# Callisto_Teknic_MSO_LED_out_v2.net
KiCad netlist of a schematic drawn in EAGLE
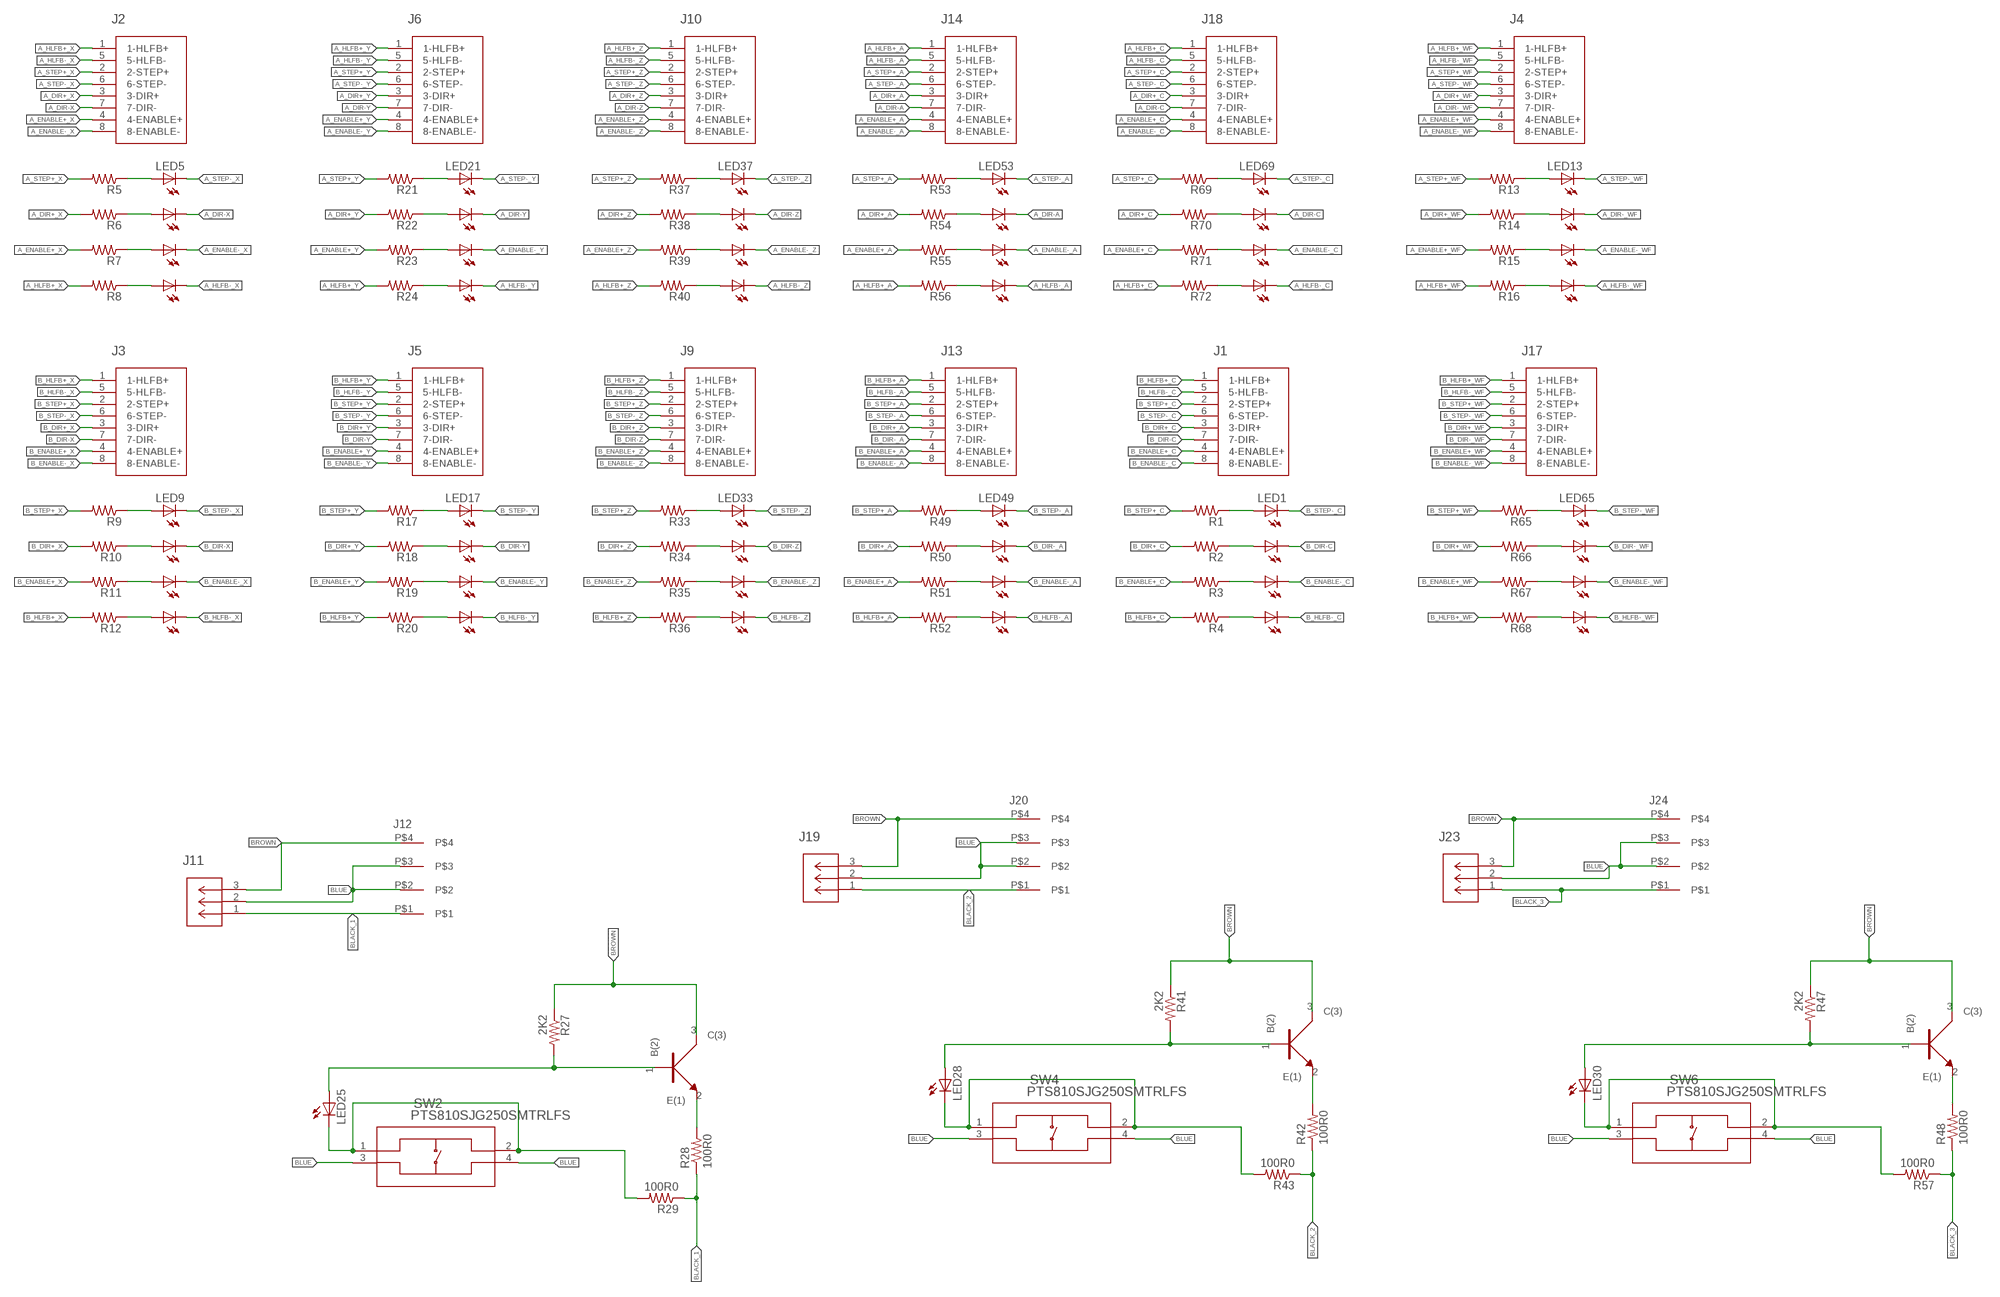
[diagram p0: schematic, sheet 1, part 1 of 2]
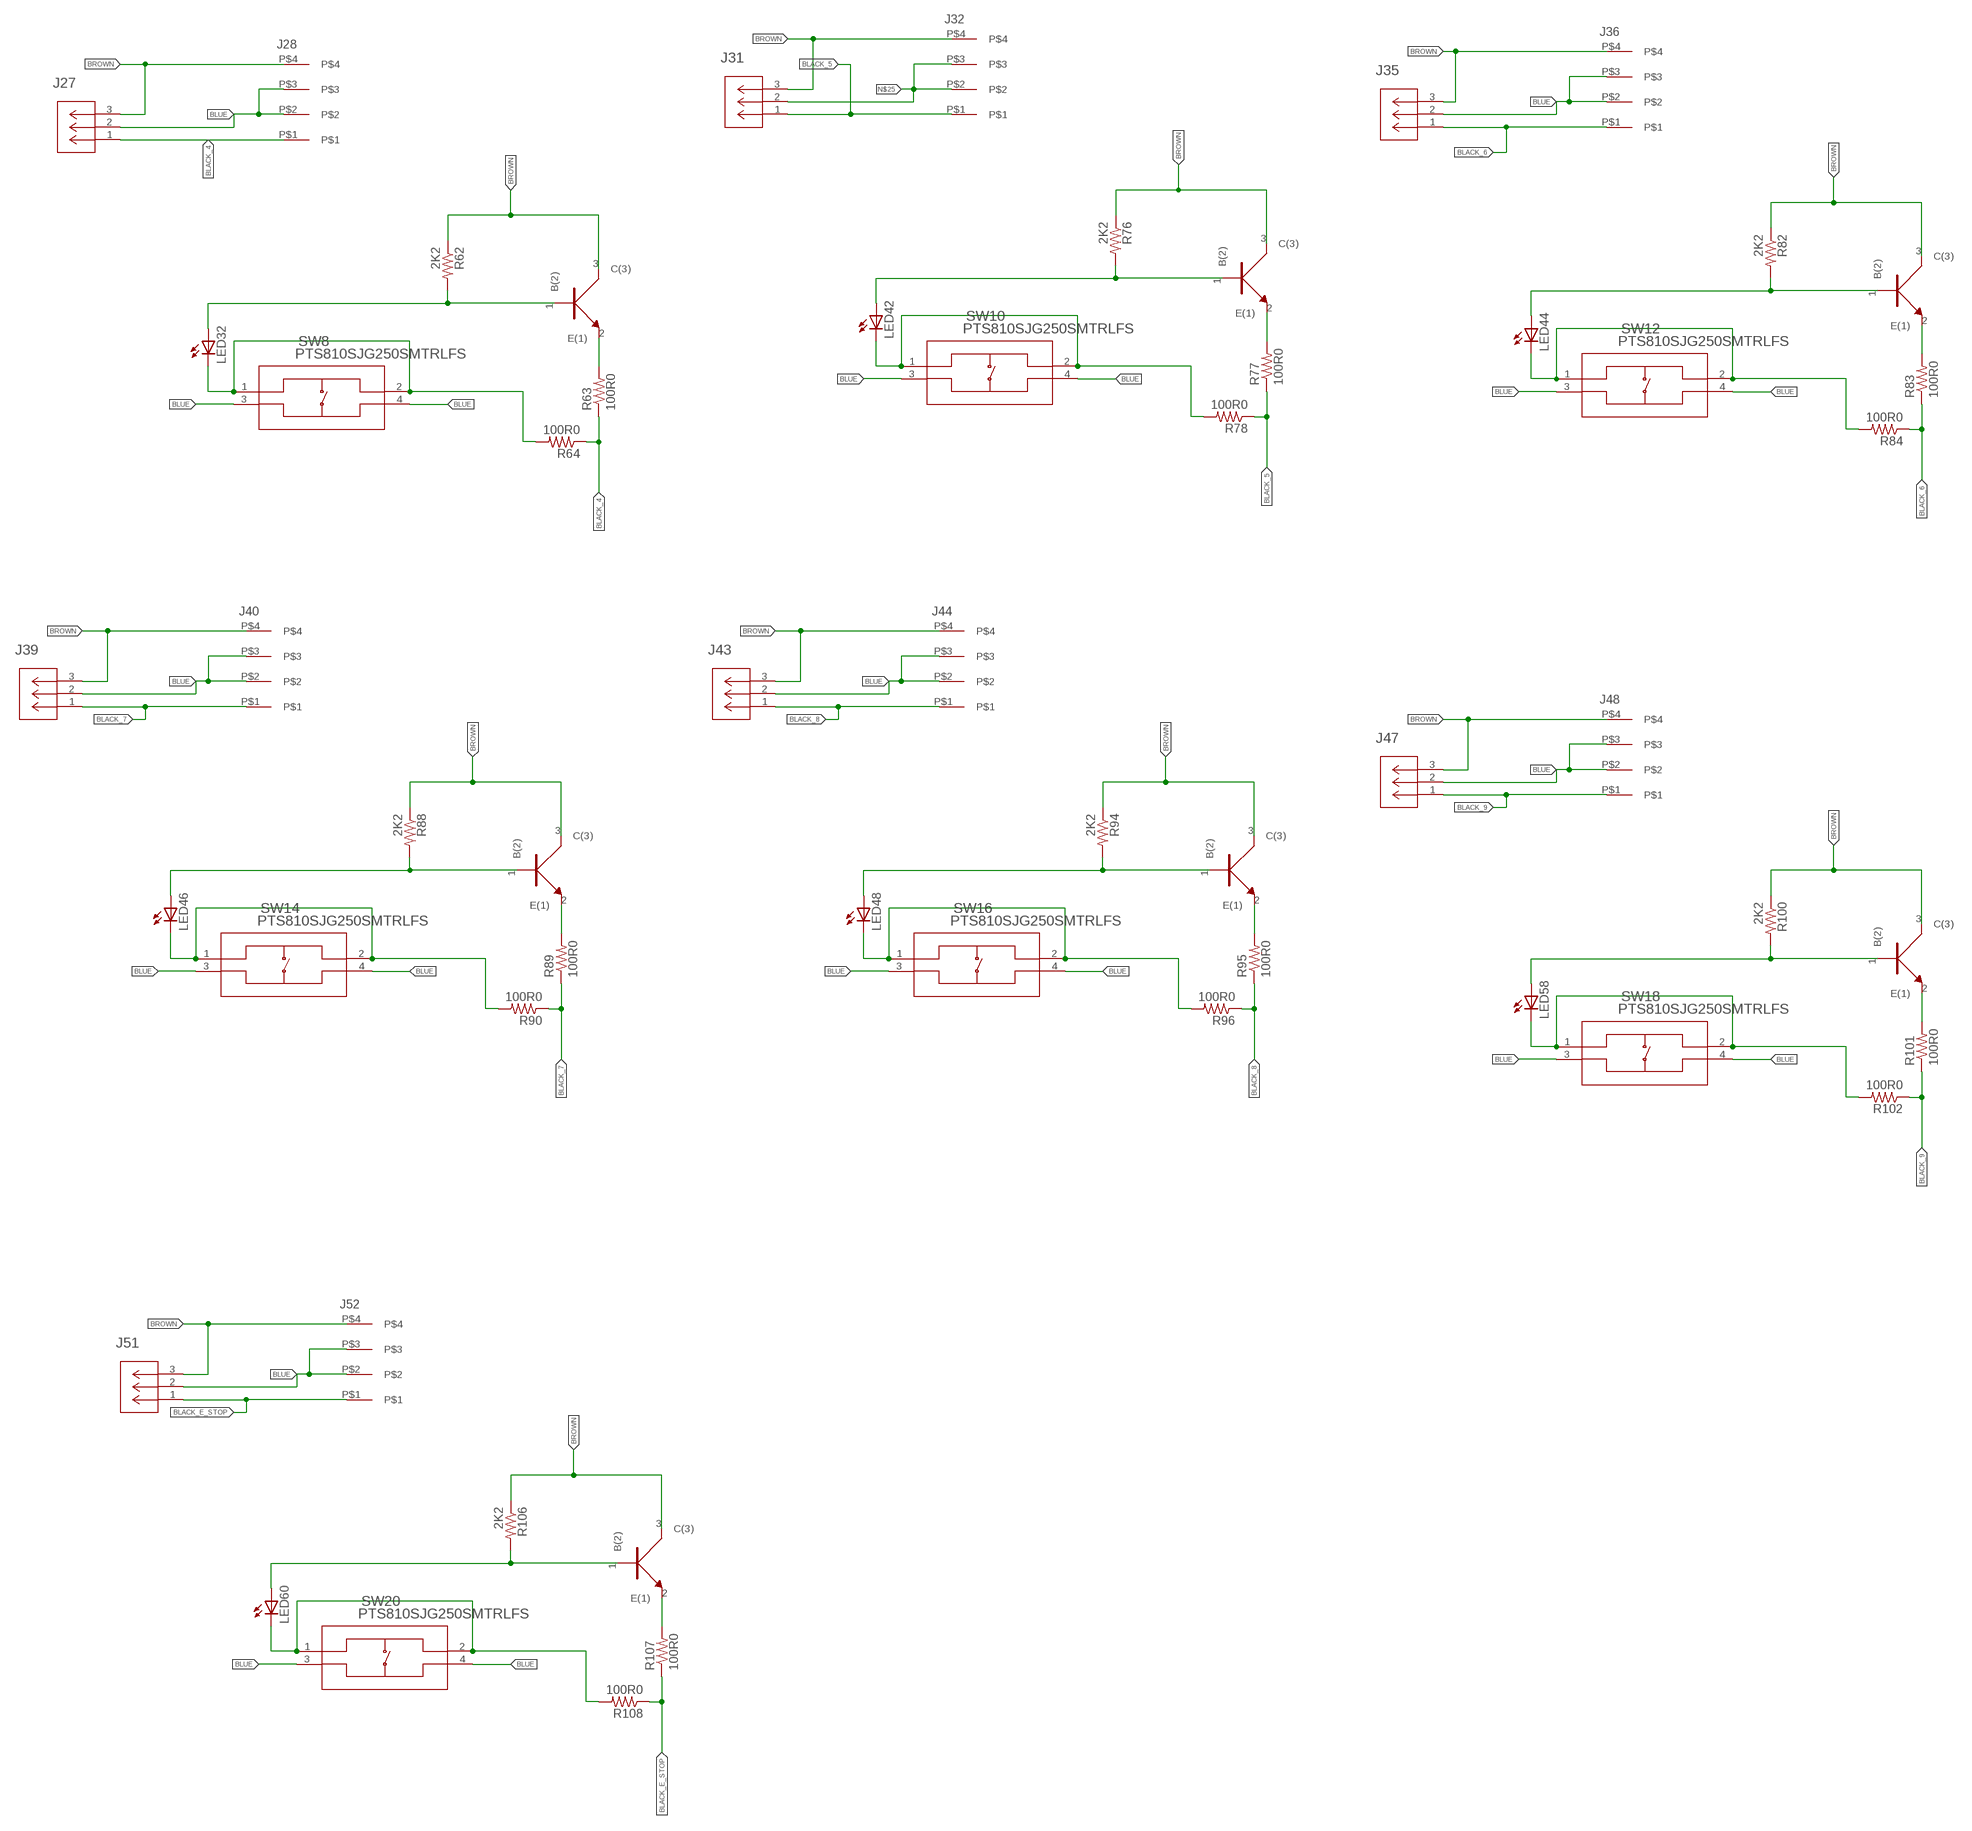
[diagram p1: schematic, sheet 1, part 2 of 2]

(export (version "E")
  (design (tool "Eeschema 10.0.6"))
  (components
    (comp (ref "J1")
      (value "TEKNIC_MOTOR_SD_8PIN")
      (footprint "eagle-import:CON_39281083")
      (fields
        (field (name "MANUFACTURER_PART_NUMBER") "39281083")
        (field (name "COPYRIGHT") "Copyright (C) 2022 Ultra Librarian. All rights reserved.")
      )
      (libsource (lib "eagle-import") (part "TEKNIC_MOTOR_SD_8PIN"))
    )
    (comp (ref "J2")
      (value "TEKNIC_MOTOR_SD_8PIN")
      (footprint "eagle-import:CON_39281083")
      (fields
        (field (name "MANUFACTURER_PART_NUMBER") "39281083")
        (field (name "COPYRIGHT") "Copyright (C) 2022 Ultra Librarian. All rights reserved.")
      )
      (libsource (lib "eagle-import") (part "TEKNIC_MOTOR_SD_8PIN"))
    )
    (comp (ref "J3")
      (value "TEKNIC_MOTOR_SD_8PIN")
      (footprint "eagle-import:CON_39281083")
      (fields
        (field (name "MANUFACTURER_PART_NUMBER") "39281083")
        (field (name "COPYRIGHT") "Copyright (C) 2022 Ultra Librarian. All rights reserved.")
      )
      (libsource (lib "eagle-import") (part "TEKNIC_MOTOR_SD_8PIN"))
    )
    (comp (ref "J4")
      (value "TEKNIC_MOTOR_SD_8PIN")
      (footprint "eagle-import:CON_39281083")
      (fields
        (field (name "MANUFACTURER_PART_NUMBER") "39281083")
        (field (name "COPYRIGHT") "Copyright (C) 2022 Ultra Librarian. All rights reserved.")
      )
      (libsource (lib "eagle-import") (part "TEKNIC_MOTOR_SD_8PIN"))
    )
    (comp (ref "J5")
      (value "TEKNIC_MOTOR_SD_8PIN")
      (footprint "eagle-import:CON_39281083")
      (fields
        (field (name "MANUFACTURER_PART_NUMBER") "39281083")
        (field (name "COPYRIGHT") "Copyright (C) 2022 Ultra Librarian. All rights reserved.")
      )
      (libsource (lib "eagle-import") (part "TEKNIC_MOTOR_SD_8PIN"))
    )
    (comp (ref "J6")
      (value "TEKNIC_MOTOR_SD_8PIN")
      (footprint "eagle-import:CON_39281083")
      (fields
        (field (name "MANUFACTURER_PART_NUMBER") "39281083")
        (field (name "COPYRIGHT") "Copyright (C) 2022 Ultra Librarian. All rights reserved.")
      )
      (libsource (lib "eagle-import") (part "TEKNIC_MOTOR_SD_8PIN"))
    )
    (comp (ref "J9")
      (value "TEKNIC_MOTOR_SD_8PIN")
      (footprint "eagle-import:CON_39281083")
      (fields
        (field (name "MANUFACTURER_PART_NUMBER") "39281083")
        (field (name "COPYRIGHT") "Copyright (C) 2022 Ultra Librarian. All rights reserved.")
      )
      (libsource (lib "eagle-import") (part "TEKNIC_MOTOR_SD_8PIN"))
    )
    (comp (ref "J10")
      (value "TEKNIC_MOTOR_SD_8PIN")
      (footprint "eagle-import:CON_39281083")
      (fields
        (field (name "MANUFACTURER_PART_NUMBER") "39281083")
        (field (name "COPYRIGHT") "Copyright (C) 2022 Ultra Librarian. All rights reserved.")
      )
      (libsource (lib "eagle-import") (part "TEKNIC_MOTOR_SD_8PIN"))
    )
    (comp (ref "J11")
      (value "CONN_530470310_PICOBLADE_X_3")
      (footprint "eagle-import:CON_530470310_MOL")
      (fields
        (field (name "MANUFACTURER_PART_NUMBER") "530470310")
        (field (name "COPYRIGHT") "Copyright (C) 2022 Ultra Librarian. All rights reserved.")
      )
      (libsource (lib "eagle-import") (part "CONN_530470310_PICOBLADE_X_3"))
    )
    (comp (ref "J12")
      (value "4-pos")
      (footprint "eagle-import:1X4_3.81MM_PITCH")
      (fields (field (name "PARTNO") "691322310004"))
      (libsource (lib "eagle-import") (part "3.81MM_1_X_4_RT_ANGLE_PLUG_HEADER"))
    )
    (comp (ref "J13")
      (value "TEKNIC_MOTOR_SD_8PIN")
      (footprint "eagle-import:CON_39281083")
      (fields
        (field (name "MANUFACTURER_PART_NUMBER") "39281083")
        (field (name "COPYRIGHT") "Copyright (C) 2022 Ultra Librarian. All rights reserved.")
      )
      (libsource (lib "eagle-import") (part "TEKNIC_MOTOR_SD_8PIN"))
    )
    (comp (ref "J14")
      (value "TEKNIC_MOTOR_SD_8PIN")
      (footprint "eagle-import:CON_39281083")
      (fields
        (field (name "MANUFACTURER_PART_NUMBER") "39281083")
        (field (name "COPYRIGHT") "Copyright (C) 2022 Ultra Librarian. All rights reserved.")
      )
      (libsource (lib "eagle-import") (part "TEKNIC_MOTOR_SD_8PIN"))
    )
    (comp (ref "J17")
      (value "TEKNIC_MOTOR_SD_8PIN")
      (footprint "eagle-import:CON_39281083")
      (fields
        (field (name "MANUFACTURER_PART_NUMBER") "39281083")
        (field (name "COPYRIGHT") "Copyright (C) 2022 Ultra Librarian. All rights reserved.")
      )
      (libsource (lib "eagle-import") (part "TEKNIC_MOTOR_SD_8PIN"))
    )
    (comp (ref "J18")
      (value "TEKNIC_MOTOR_SD_8PIN")
      (footprint "eagle-import:CON_39281083")
      (fields
        (field (name "MANUFACTURER_PART_NUMBER") "39281083")
        (field (name "COPYRIGHT") "Copyright (C) 2022 Ultra Librarian. All rights reserved.")
      )
      (libsource (lib "eagle-import") (part "TEKNIC_MOTOR_SD_8PIN"))
    )
    (comp (ref "J19")
      (value "CONN_530470310_PICOBLADE_X_3")
      (footprint "eagle-import:CON_530470310_MOL")
      (fields
        (field (name "MANUFACTURER_PART_NUMBER") "530470310")
        (field (name "COPYRIGHT") "Copyright (C) 2022 Ultra Librarian. All rights reserved.")
      )
      (libsource (lib "eagle-import") (part "CONN_530470310_PICOBLADE_X_3"))
    )
    (comp (ref "J20")
      (value "4-pos")
      (footprint "eagle-import:1X4_3.81MM_PITCH")
      (fields (field (name "PARTNO") "691322310004"))
      (libsource (lib "eagle-import") (part "3.81MM_1_X_4_RT_ANGLE_PLUG_HEADER"))
    )
    (comp (ref "J23")
      (value "CONN_530470310_PICOBLADE_X_3")
      (footprint "eagle-import:CON_530470310_MOL")
      (fields
        (field (name "MANUFACTURER_PART_NUMBER") "530470310")
        (field (name "COPYRIGHT") "Copyright (C) 2022 Ultra Librarian. All rights reserved.")
      )
      (libsource (lib "eagle-import") (part "CONN_530470310_PICOBLADE_X_3"))
    )
    (comp (ref "J24")
      (value "4-pos")
      (footprint "eagle-import:1X4_3.81MM_PITCH")
      (fields (field (name "PARTNO") "691322310004"))
      (libsource (lib "eagle-import") (part "3.81MM_1_X_4_RT_ANGLE_PLUG_HEADER"))
    )
    (comp (ref "J27")
      (value "CONN_530470310_PICOBLADE_X_3")
      (footprint "eagle-import:CON_530470310_MOL")
      (fields
        (field (name "MANUFACTURER_PART_NUMBER") "530470310")
        (field (name "COPYRIGHT") "Copyright (C) 2022 Ultra Librarian. All rights reserved.")
      )
      (libsource (lib "eagle-import") (part "CONN_530470310_PICOBLADE_X_3"))
    )
    (comp (ref "J28")
      (value "4-pos")
      (footprint "eagle-import:1X4_3.81MM_PITCH")
      (fields (field (name "PARTNO") "691322310004"))
      (libsource (lib "eagle-import") (part "3.81MM_1_X_4_RT_ANGLE_PLUG_HEADER"))
    )
    (comp (ref "J31")
      (value "CONN_530470310_PICOBLADE_X_3")
      (footprint "eagle-import:CON_530470310_MOL")
      (fields
        (field (name "MANUFACTURER_PART_NUMBER") "530470310")
        (field (name "COPYRIGHT") "Copyright (C) 2022 Ultra Librarian. All rights reserved.")
      )
      (libsource (lib "eagle-import") (part "CONN_530470310_PICOBLADE_X_3"))
    )
    (comp (ref "J32")
      (value "4-pos")
      (footprint "eagle-import:1X4_3.81MM_PITCH")
      (fields (field (name "PARTNO") "691322310004"))
      (libsource (lib "eagle-import") (part "3.81MM_1_X_4_RT_ANGLE_PLUG_HEADER"))
    )
    (comp (ref "J35")
      (value "CONN_530470310_PICOBLADE_X_3")
      (footprint "eagle-import:CON_530470310_MOL")
      (fields
        (field (name "MANUFACTURER_PART_NUMBER") "530470310")
        (field (name "COPYRIGHT") "Copyright (C) 2022 Ultra Librarian. All rights reserved.")
      )
      (libsource (lib "eagle-import") (part "CONN_530470310_PICOBLADE_X_3"))
    )
    (comp (ref "J36")
      (value "4-pos")
      (footprint "eagle-import:1X4_3.81MM_PITCH")
      (fields (field (name "PARTNO") "691322310004"))
      (libsource (lib "eagle-import") (part "3.81MM_1_X_4_RT_ANGLE_PLUG_HEADER"))
    )
    (comp (ref "J39")
      (value "CONN_530470310_PICOBLADE_X_3")
      (footprint "eagle-import:CON_530470310_MOL")
      (fields
        (field (name "MANUFACTURER_PART_NUMBER") "530470310")
        (field (name "COPYRIGHT") "Copyright (C) 2022 Ultra Librarian. All rights reserved.")
      )
      (libsource (lib "eagle-import") (part "CONN_530470310_PICOBLADE_X_3"))
    )
    (comp (ref "J40")
      (value "4-pos")
      (footprint "eagle-import:1X4_3.81MM_PITCH")
      (fields (field (name "PARTNO") "691322310004"))
      (libsource (lib "eagle-import") (part "3.81MM_1_X_4_RT_ANGLE_PLUG_HEADER"))
    )
    (comp (ref "J43")
      (value "CONN_530470310_PICOBLADE_X_3")
      (footprint "eagle-import:CON_530470310_MOL")
      (fields
        (field (name "MANUFACTURER_PART_NUMBER") "530470310")
        (field (name "COPYRIGHT") "Copyright (C) 2022 Ultra Librarian. All rights reserved.")
      )
      (libsource (lib "eagle-import") (part "CONN_530470310_PICOBLADE_X_3"))
    )
    (comp (ref "J44")
      (value "4-pos")
      (footprint "eagle-import:1X4_3.81MM_PITCH")
      (fields (field (name "PARTNO") "691322310004"))
      (libsource (lib "eagle-import") (part "3.81MM_1_X_4_RT_ANGLE_PLUG_HEADER"))
    )
    (comp (ref "J47")
      (value "CONN_530470310_PICOBLADE_X_3")
      (footprint "eagle-import:CON_530470310_MOL")
      (fields
        (field (name "MANUFACTURER_PART_NUMBER") "530470310")
        (field (name "COPYRIGHT") "Copyright (C) 2022 Ultra Librarian. All rights reserved.")
      )
      (libsource (lib "eagle-import") (part "CONN_530470310_PICOBLADE_X_3"))
    )
    (comp (ref "J48")
      (value "4-pos")
      (footprint "eagle-import:1X4_3.81MM_PITCH")
      (fields (field (name "PARTNO") "691322310004"))
      (libsource (lib "eagle-import") (part "3.81MM_1_X_4_RT_ANGLE_PLUG_HEADER"))
    )
    (comp (ref "J51")
      (value "CONN_530470310_PICOBLADE_X_3")
      (footprint "eagle-import:CON_530470310_MOL")
      (fields
        (field (name "MANUFACTURER_PART_NUMBER") "530470310")
        (field (name "COPYRIGHT") "Copyright (C) 2022 Ultra Librarian. All rights reserved.")
      )
      (libsource (lib "eagle-import") (part "CONN_530470310_PICOBLADE_X_3"))
    )
    (comp (ref "J52")
      (value "4-pos")
      (footprint "eagle-import:1X4_3.81MM_PITCH")
      (fields (field (name "PARTNO") "691322310004"))
      (libsource (lib "eagle-import") (part "3.81MM_1_X_4_RT_ANGLE_PLUG_HEADER"))
    )
    (comp (ref "LED1")
      (value "Green")
      (footprint "eagle-import:0805")
      (fields (field (name "PARTNO") "LG R971-KN-1"))
      (libsource (lib "eagle-import") (part "LED_0805_GREEN"))
    )
    (comp (ref "LED2")
      (value "Green")
      (footprint "eagle-import:0805")
      (fields (field (name "PARTNO") "LG R971-KN-1"))
      (libsource (lib "eagle-import") (part "LED_0805_GREEN"))
    )
    (comp (ref "LED3")
      (value "Green")
      (footprint "eagle-import:0805")
      (fields (field (name "PARTNO") "LG R971-KN-1"))
      (libsource (lib "eagle-import") (part "LED_0805_GREEN"))
    )
    (comp (ref "LED4")
      (value "Green")
      (footprint "eagle-import:0805")
      (fields (field (name "PARTNO") "LG R971-KN-1"))
      (libsource (lib "eagle-import") (part "LED_0805_GREEN"))
    )
    (comp (ref "LED5")
      (value "Green")
      (footprint "eagle-import:0805")
      (fields (field (name "PARTNO") "LG R971-KN-1"))
      (libsource (lib "eagle-import") (part "LED_0805_GREEN"))
    )
    (comp (ref "LED6")
      (value "Green")
      (footprint "eagle-import:0805")
      (fields (field (name "PARTNO") "LG R971-KN-1"))
      (libsource (lib "eagle-import") (part "LED_0805_GREEN"))
    )
    (comp (ref "LED7")
      (value "Green")
      (footprint "eagle-import:0805")
      (fields (field (name "PARTNO") "LG R971-KN-1"))
      (libsource (lib "eagle-import") (part "LED_0805_GREEN"))
    )
    (comp (ref "LED8")
      (value "Green")
      (footprint "eagle-import:0805")
      (fields (field (name "PARTNO") "LG R971-KN-1"))
      (libsource (lib "eagle-import") (part "LED_0805_GREEN"))
    )
    (comp (ref "LED9")
      (value "Green")
      (footprint "eagle-import:0805")
      (fields (field (name "PARTNO") "LG R971-KN-1"))
      (libsource (lib "eagle-import") (part "LED_0805_GREEN"))
    )
    (comp (ref "LED10")
      (value "Green")
      (footprint "eagle-import:0805")
      (fields (field (name "PARTNO") "LG R971-KN-1"))
      (libsource (lib "eagle-import") (part "LED_0805_GREEN"))
    )
    (comp (ref "LED11")
      (value "Green")
      (footprint "eagle-import:0805")
      (fields (field (name "PARTNO") "LG R971-KN-1"))
      (libsource (lib "eagle-import") (part "LED_0805_GREEN"))
    )
    (comp (ref "LED12")
      (value "Green")
      (footprint "eagle-import:0805")
      (fields (field (name "PARTNO") "LG R971-KN-1"))
      (libsource (lib "eagle-import") (part "LED_0805_GREEN"))
    )
    (comp (ref "LED13")
      (value "Green")
      (footprint "eagle-import:0805")
      (fields (field (name "PARTNO") "LG R971-KN-1"))
      (libsource (lib "eagle-import") (part "LED_0805_GREEN"))
    )
    (comp (ref "LED14")
      (value "Green")
      (footprint "eagle-import:0805")
      (fields (field (name "PARTNO") "LG R971-KN-1"))
      (libsource (lib "eagle-import") (part "LED_0805_GREEN"))
    )
    (comp (ref "LED15")
      (value "Green")
      (footprint "eagle-import:0805")
      (fields (field (name "PARTNO") "LG R971-KN-1"))
      (libsource (lib "eagle-import") (part "LED_0805_GREEN"))
    )
    (comp (ref "LED16")
      (value "Green")
      (footprint "eagle-import:0805")
      (fields (field (name "PARTNO") "LG R971-KN-1"))
      (libsource (lib "eagle-import") (part "LED_0805_GREEN"))
    )
    (comp (ref "LED17")
      (value "Green")
      (footprint "eagle-import:0805")
      (fields (field (name "PARTNO") "LG R971-KN-1"))
      (libsource (lib "eagle-import") (part "LED_0805_GREEN"))
    )
    (comp (ref "LED18")
      (value "Green")
      (footprint "eagle-import:0805")
      (fields (field (name "PARTNO") "LG R971-KN-1"))
      (libsource (lib "eagle-import") (part "LED_0805_GREEN"))
    )
    (comp (ref "LED19")
      (value "Green")
      (footprint "eagle-import:0805")
      (fields (field (name "PARTNO") "LG R971-KN-1"))
      (libsource (lib "eagle-import") (part "LED_0805_GREEN"))
    )
    (comp (ref "LED20")
      (value "Green")
      (footprint "eagle-import:0805")
      (fields (field (name "PARTNO") "LG R971-KN-1"))
      (libsource (lib "eagle-import") (part "LED_0805_GREEN"))
    )
    (comp (ref "LED21")
      (value "Green")
      (footprint "eagle-import:0805")
      (fields (field (name "PARTNO") "LG R971-KN-1"))
      (libsource (lib "eagle-import") (part "LED_0805_GREEN"))
    )
    (comp (ref "LED22")
      (value "Green")
      (footprint "eagle-import:0805")
      (fields (field (name "PARTNO") "LG R971-KN-1"))
      (libsource (lib "eagle-import") (part "LED_0805_GREEN"))
    )
    (comp (ref "LED23")
      (value "Green")
      (footprint "eagle-import:0805")
      (fields (field (name "PARTNO") "LG R971-KN-1"))
      (libsource (lib "eagle-import") (part "LED_0805_GREEN"))
    )
    (comp (ref "LED24")
      (value "Green")
      (footprint "eagle-import:0805")
      (fields (field (name "PARTNO") "LG R971-KN-1"))
      (libsource (lib "eagle-import") (part "LED_0805_GREEN"))
    )
    (comp (ref "LED25")
      (value "Green")
      (footprint "eagle-import:0805")
      (fields (field (name "PARTNO") "LG R971-KN-1"))
      (libsource (lib "eagle-import") (part "LED_0805_GREEN"))
    )
    (comp (ref "LED28")
      (value "Green")
      (footprint "eagle-import:0805")
      (fields (field (name "PARTNO") "LG R971-KN-1"))
      (libsource (lib "eagle-import") (part "LED_0805_GREEN"))
    )
    (comp (ref "LED30")
      (value "Green")
      (footprint "eagle-import:0805")
      (fields (field (name "PARTNO") "LG R971-KN-1"))
      (libsource (lib "eagle-import") (part "LED_0805_GREEN"))
    )
    (comp (ref "LED32")
      (value "Green")
      (footprint "eagle-import:0805")
      (fields (field (name "PARTNO") "LG R971-KN-1"))
      (libsource (lib "eagle-import") (part "LED_0805_GREEN"))
    )
    (comp (ref "LED33")
      (value "Green")
      (footprint "eagle-import:0805")
      (fields (field (name "PARTNO") "LG R971-KN-1"))
      (libsource (lib "eagle-import") (part "LED_0805_GREEN"))
    )
    (comp (ref "LED34")
      (value "Green")
      (footprint "eagle-import:0805")
      (fields (field (name "PARTNO") "LG R971-KN-1"))
      (libsource (lib "eagle-import") (part "LED_0805_GREEN"))
    )
    (comp (ref "LED35")
      (value "Green")
      (footprint "eagle-import:0805")
      (fields (field (name "PARTNO") "LG R971-KN-1"))
      (libsource (lib "eagle-import") (part "LED_0805_GREEN"))
    )
    (comp (ref "LED36")
      (value "Green")
      (footprint "eagle-import:0805")
      (fields (field (name "PARTNO") "LG R971-KN-1"))
      (libsource (lib "eagle-import") (part "LED_0805_GREEN"))
    )
    (comp (ref "LED37")
      (value "Green")
      (footprint "eagle-import:0805")
      (fields (field (name "PARTNO") "LG R971-KN-1"))
      (libsource (lib "eagle-import") (part "LED_0805_GREEN"))
    )
    (comp (ref "LED38")
      (value "Green")
      (footprint "eagle-import:0805")
      (fields (field (name "PARTNO") "LG R971-KN-1"))
      (libsource (lib "eagle-import") (part "LED_0805_GREEN"))
    )
    (comp (ref "LED39")
      (value "Green")
      (footprint "eagle-import:0805")
      (fields (field (name "PARTNO") "LG R971-KN-1"))
      (libsource (lib "eagle-import") (part "LED_0805_GREEN"))
    )
    (comp (ref "LED40")
      (value "Green")
      (footprint "eagle-import:0805")
      (fields (field (name "PARTNO") "LG R971-KN-1"))
      (libsource (lib "eagle-import") (part "LED_0805_GREEN"))
    )
    (comp (ref "LED42")
      (value "Green")
      (footprint "eagle-import:0805")
      (fields (field (name "PARTNO") "LG R971-KN-1"))
      (libsource (lib "eagle-import") (part "LED_0805_GREEN"))
    )
    (comp (ref "LED44")
      (value "Green")
      (footprint "eagle-import:0805")
      (fields (field (name "PARTNO") "LG R971-KN-1"))
      (libsource (lib "eagle-import") (part "LED_0805_GREEN"))
    )
    (comp (ref "LED46")
      (value "Green")
      (footprint "eagle-import:0805")
      (fields (field (name "PARTNO") "LG R971-KN-1"))
      (libsource (lib "eagle-import") (part "LED_0805_GREEN"))
    )
    (comp (ref "LED48")
      (value "Green")
      (footprint "eagle-import:0805")
      (fields (field (name "PARTNO") "LG R971-KN-1"))
      (libsource (lib "eagle-import") (part "LED_0805_GREEN"))
    )
    (comp (ref "LED49")
      (value "Green")
      (footprint "eagle-import:0805")
      (fields (field (name "PARTNO") "LG R971-KN-1"))
      (libsource (lib "eagle-import") (part "LED_0805_GREEN"))
    )
    (comp (ref "LED50")
      (value "Green")
      (footprint "eagle-import:0805")
      (fields (field (name "PARTNO") "LG R971-KN-1"))
      (libsource (lib "eagle-import") (part "LED_0805_GREEN"))
    )
    (comp (ref "LED51")
      (value "Green")
      (footprint "eagle-import:0805")
      (fields (field (name "PARTNO") "LG R971-KN-1"))
      (libsource (lib "eagle-import") (part "LED_0805_GREEN"))
    )
    (comp (ref "LED52")
      (value "Green")
      (footprint "eagle-import:0805")
      (fields (field (name "PARTNO") "LG R971-KN-1"))
      (libsource (lib "eagle-import") (part "LED_0805_GREEN"))
    )
    (comp (ref "LED53")
      (value "Green")
      (footprint "eagle-import:0805")
      (fields (field (name "PARTNO") "LG R971-KN-1"))
      (libsource (lib "eagle-import") (part "LED_0805_GREEN"))
    )
    (comp (ref "LED54")
      (value "Green")
      (footprint "eagle-import:0805")
      (fields (field (name "PARTNO") "LG R971-KN-1"))
      (libsource (lib "eagle-import") (part "LED_0805_GREEN"))
    )
    (comp (ref "LED55")
      (value "Green")
      (footprint "eagle-import:0805")
      (fields (field (name "PARTNO") "LG R971-KN-1"))
      (libsource (lib "eagle-import") (part "LED_0805_GREEN"))
    )
    (comp (ref "LED56")
      (value "Green")
      (footprint "eagle-import:0805")
      (fields (field (name "PARTNO") "LG R971-KN-1"))
      (libsource (lib "eagle-import") (part "LED_0805_GREEN"))
    )
    (comp (ref "LED58")
      (value "Green")
      (footprint "eagle-import:0805")
      (fields (field (name "PARTNO") "LG R971-KN-1"))
      (libsource (lib "eagle-import") (part "LED_0805_GREEN"))
    )
    (comp (ref "LED60")
      (value "Green")
      (footprint "eagle-import:0805")
      (fields (field (name "PARTNO") "LG R971-KN-1"))
      (libsource (lib "eagle-import") (part "LED_0805_GREEN"))
    )
    (comp (ref "LED65")
      (value "Green")
      (footprint "eagle-import:0805")
      (fields (field (name "PARTNO") "LG R971-KN-1"))
      (libsource (lib "eagle-import") (part "LED_0805_GREEN"))
    )
    (comp (ref "LED66")
      (value "Green")
      (footprint "eagle-import:0805")
      (fields (field (name "PARTNO") "LG R971-KN-1"))
      (libsource (lib "eagle-import") (part "LED_0805_GREEN"))
    )
    (comp (ref "LED67")
      (value "Green")
      (footprint "eagle-import:0805")
      (fields (field (name "PARTNO") "LG R971-KN-1"))
      (libsource (lib "eagle-import") (part "LED_0805_GREEN"))
    )
    (comp (ref "LED68")
      (value "Green")
      (footprint "eagle-import:0805")
      (fields (field (name "PARTNO") "LG R971-KN-1"))
      (libsource (lib "eagle-import") (part "LED_0805_GREEN"))
    )
    (comp (ref "LED69")
      (value "Green")
      (footprint "eagle-import:0805")
      (fields (field (name "PARTNO") "LG R971-KN-1"))
      (libsource (lib "eagle-import") (part "LED_0805_GREEN"))
    )
    (comp (ref "LED70")
      (value "Green")
      (footprint "eagle-import:0805")
      (fields (field (name "PARTNO") "LG R971-KN-1"))
      (libsource (lib "eagle-import") (part "LED_0805_GREEN"))
    )
    (comp (ref "LED71")
      (value "Green")
      (footprint "eagle-import:0805")
      (fields (field (name "PARTNO") "LG R971-KN-1"))
      (libsource (lib "eagle-import") (part "LED_0805_GREEN"))
    )
    (comp (ref "LED72")
      (value "Green")
      (footprint "eagle-import:0805")
      (fields (field (name "PARTNO") "LG R971-KN-1"))
      (libsource (lib "eagle-import") (part "LED_0805_GREEN"))
    )
    (comp (ref "R1")
      (value "R_0805")
      (footprint "eagle-import:0805")
      (libsource (lib "eagle-import") (part "R_0805"))
    )
    (comp (ref "R2")
      (value "R_0805")
      (footprint "eagle-import:0805")
      (libsource (lib "eagle-import") (part "R_0805"))
    )
    (comp (ref "R3")
      (value "R_0805")
      (footprint "eagle-import:0805")
      (libsource (lib "eagle-import") (part "R_0805"))
    )
    (comp (ref "R4")
      (value "R_0805")
      (footprint "eagle-import:0805")
      (libsource (lib "eagle-import") (part "R_0805"))
    )
    (comp (ref "R5")
      (value "R_0805")
      (footprint "eagle-import:0805")
      (libsource (lib "eagle-import") (part "R_0805"))
    )
    (comp (ref "R6")
      (value "R_0805")
      (footprint "eagle-import:0805")
      (libsource (lib "eagle-import") (part "R_0805"))
    )
    (comp (ref "R7")
      (value "R_0805")
      (footprint "eagle-import:0805")
      (libsource (lib "eagle-import") (part "R_0805"))
    )
    (comp (ref "R8")
      (value "R_0805")
      (footprint "eagle-import:0805")
      (libsource (lib "eagle-import") (part "R_0805"))
    )
    (comp (ref "R9")
      (value "R_0805")
      (footprint "eagle-import:0805")
      (libsource (lib "eagle-import") (part "R_0805"))
    )
    (comp (ref "R10")
      (value "R_0805")
      (footprint "eagle-import:0805")
      (libsource (lib "eagle-import") (part "R_0805"))
    )
    (comp (ref "R11")
      (value "R_0805")
      (footprint "eagle-import:0805")
      (libsource (lib "eagle-import") (part "R_0805"))
    )
    (comp (ref "R12")
      (value "R_0805")
      (footprint "eagle-import:0805")
      (libsource (lib "eagle-import") (part "R_0805"))
    )
    (comp (ref "R13")
      (value "R_0805")
      (footprint "eagle-import:0805")
      (libsource (lib "eagle-import") (part "R_0805"))
    )
    (comp (ref "R14")
      (value "R_0805")
      (footprint "eagle-import:0805")
      (libsource (lib "eagle-import") (part "R_0805"))
    )
    (comp (ref "R15")
      (value "R_0805")
      (footprint "eagle-import:0805")
      (libsource (lib "eagle-import") (part "R_0805"))
    )
    (comp (ref "R16")
      (value "R_0805")
      (footprint "eagle-import:0805")
      (libsource (lib "eagle-import") (part "R_0805"))
    )
    (comp (ref "R17")
      (value "R_0805")
      (footprint "eagle-import:0805")
      (libsource (lib "eagle-import") (part "R_0805"))
    )
    (comp (ref "R18")
      (value "R_0805")
      (footprint "eagle-import:0805")
      (libsource (lib "eagle-import") (part "R_0805"))
    )
    (comp (ref "R19")
      (value "R_0805")
      (footprint "eagle-import:0805")
      (libsource (lib "eagle-import") (part "R_0805"))
    )
    (comp (ref "R20")
      (value "R_0805")
      (footprint "eagle-import:0805")
      (libsource (lib "eagle-import") (part "R_0805"))
    )
    (comp (ref "R21")
      (value "R_0805")
      (footprint "eagle-import:0805")
      (libsource (lib "eagle-import") (part "R_0805"))
    )
    (comp (ref "R22")
      (value "R_0805")
      (footprint "eagle-import:0805")
      (libsource (lib "eagle-import") (part "R_0805"))
    )
    (comp (ref "R23")
      (value "R_0805")
      (footprint "eagle-import:0805")
      (libsource (lib "eagle-import") (part "R_0805"))
    )
    (comp (ref "R24")
      (value "R_0805")
      (footprint "eagle-import:0805")
      (libsource (lib "eagle-import") (part "R_0805"))
    )
    (comp (ref "R27")
      (value "2K2")
      (footprint "eagle-import:0402")
      (libsource (lib "eagle-import") (part "R_0402"))
    )
    (comp (ref "R28")
      (value "100R0")
      (footprint "eagle-import:0402")
      (libsource (lib "eagle-import") (part "R_0402"))
    )
    (comp (ref "R29")
      (value "100R0")
      (footprint "eagle-import:0402")
      (libsource (lib "eagle-import") (part "R_0402"))
    )
    (comp (ref "R33")
      (value "R_0805")
      (footprint "eagle-import:0805")
      (libsource (lib "eagle-import") (part "R_0805"))
    )
    (comp (ref "R34")
      (value "R_0805")
      (footprint "eagle-import:0805")
      (libsource (lib "eagle-import") (part "R_0805"))
    )
    (comp (ref "R35")
      (value "R_0805")
      (footprint "eagle-import:0805")
      (libsource (lib "eagle-import") (part "R_0805"))
    )
    (comp (ref "R36")
      (value "R_0805")
      (footprint "eagle-import:0805")
      (libsource (lib "eagle-import") (part "R_0805"))
    )
    (comp (ref "R37")
      (value "R_0805")
      (footprint "eagle-import:0805")
      (libsource (lib "eagle-import") (part "R_0805"))
    )
    (comp (ref "R38")
      (value "R_0805")
      (footprint "eagle-import:0805")
      (libsource (lib "eagle-import") (part "R_0805"))
    )
    (comp (ref "R39")
      (value "R_0805")
      (footprint "eagle-import:0805")
      (libsource (lib "eagle-import") (part "R_0805"))
    )
    (comp (ref "R40")
      (value "R_0805")
      (footprint "eagle-import:0805")
      (libsource (lib "eagle-import") (part "R_0805"))
    )
    (comp (ref "R41")
      (value "2K2")
      (footprint "eagle-import:0402")
      (libsource (lib "eagle-import") (part "R_0402"))
    )
    (comp (ref "R42")
      (value "100R0")
      (footprint "eagle-import:0402")
      (libsource (lib "eagle-import") (part "R_0402"))
    )
    (comp (ref "R43")
      (value "100R0")
      (footprint "eagle-import:0402")
      (libsource (lib "eagle-import") (part "R_0402"))
    )
    (comp (ref "R47")
      (value "2K2")
      (footprint "eagle-import:0402")
      (libsource (lib "eagle-import") (part "R_0402"))
    )
    (comp (ref "R48")
      (value "100R0")
      (footprint "eagle-import:0402")
      (libsource (lib "eagle-import") (part "R_0402"))
    )
    (comp (ref "R49")
      (value "R_0805")
      (footprint "eagle-import:0805")
      (libsource (lib "eagle-import") (part "R_0805"))
    )
    (comp (ref "R50")
      (value "R_0805")
      (footprint "eagle-import:0805")
      (libsource (lib "eagle-import") (part "R_0805"))
    )
    (comp (ref "R51")
      (value "R_0805")
      (footprint "eagle-import:0805")
      (libsource (lib "eagle-import") (part "R_0805"))
    )
    (comp (ref "R52")
      (value "R_0805")
      (footprint "eagle-import:0805")
      (libsource (lib "eagle-import") (part "R_0805"))
    )
    (comp (ref "R53")
      (value "R_0805")
      (footprint "eagle-import:0805")
      (libsource (lib "eagle-import") (part "R_0805"))
    )
    (comp (ref "R54")
      (value "R_0805")
      (footprint "eagle-import:0805")
      (libsource (lib "eagle-import") (part "R_0805"))
    )
    (comp (ref "R55")
      (value "R_0805")
      (footprint "eagle-import:0805")
      (libsource (lib "eagle-import") (part "R_0805"))
    )
    (comp (ref "R56")
      (value "R_0805")
      (footprint "eagle-import:0805")
      (libsource (lib "eagle-import") (part "R_0805"))
    )
    (comp (ref "R57")
      (value "100R0")
      (footprint "eagle-import:0402")
      (libsource (lib "eagle-import") (part "R_0402"))
    )
    (comp (ref "R62")
      (value "2K2")
      (footprint "eagle-import:0402")
      (libsource (lib "eagle-import") (part "R_0402"))
    )
    (comp (ref "R63")
      (value "100R0")
      (footprint "eagle-import:0402")
      (libsource (lib "eagle-import") (part "R_0402"))
    )
    (comp (ref "R64")
      (value "100R0")
      (footprint "eagle-import:0402")
      (libsource (lib "eagle-import") (part "R_0402"))
    )
    (comp (ref "R65")
      (value "R_0805")
      (footprint "eagle-import:0805")
      (libsource (lib "eagle-import") (part "R_0805"))
    )
    (comp (ref "R66")
      (value "R_0805")
      (footprint "eagle-import:0805")
      (libsource (lib "eagle-import") (part "R_0805"))
    )
    (comp (ref "R67")
      (value "R_0805")
      (footprint "eagle-import:0805")
      (libsource (lib "eagle-import") (part "R_0805"))
    )
    (comp (ref "R68")
      (value "R_0805")
      (footprint "eagle-import:0805")
      (libsource (lib "eagle-import") (part "R_0805"))
    )
    (comp (ref "R69")
      (value "R_0805")
      (footprint "eagle-import:0805")
      (libsource (lib "eagle-import") (part "R_0805"))
    )
    (comp (ref "R70")
      (value "R_0805")
      (footprint "eagle-import:0805")
      (libsource (lib "eagle-import") (part "R_0805"))
    )
    (comp (ref "R71")
      (value "R_0805")
      (footprint "eagle-import:0805")
      (libsource (lib "eagle-import") (part "R_0805"))
    )
    (comp (ref "R72")
      (value "R_0805")
      (footprint "eagle-import:0805")
      (libsource (lib "eagle-import") (part "R_0805"))
    )
    (comp (ref "R76")
      (value "2K2")
      (footprint "eagle-import:0402")
      (libsource (lib "eagle-import") (part "R_0402"))
    )
    (comp (ref "R77")
      (value "100R0")
      (footprint "eagle-import:0402")
      (libsource (lib "eagle-import") (part "R_0402"))
    )
    (comp (ref "R78")
      (value "100R0")
      (footprint "eagle-import:0402")
      (libsource (lib "eagle-import") (part "R_0402"))
    )
    (comp (ref "R82")
      (value "2K2")
      (footprint "eagle-import:0402")
      (libsource (lib "eagle-import") (part "R_0402"))
    )
    (comp (ref "R83")
      (value "100R0")
      (footprint "eagle-import:0402")
      (libsource (lib "eagle-import") (part "R_0402"))
    )
    (comp (ref "R84")
      (value "100R0")
      (footprint "eagle-import:0402")
      (libsource (lib "eagle-import") (part "R_0402"))
    )
    (comp (ref "R88")
      (value "2K2")
      (footprint "eagle-import:0402")
      (libsource (lib "eagle-import") (part "R_0402"))
    )
    (comp (ref "R89")
      (value "100R0")
      (footprint "eagle-import:0402")
      (libsource (lib "eagle-import") (part "R_0402"))
    )
    (comp (ref "R90")
      (value "100R0")
      (footprint "eagle-import:0402")
      (libsource (lib "eagle-import") (part "R_0402"))
    )
    (comp (ref "R94")
      (value "2K2")
      (footprint "eagle-import:0402")
      (libsource (lib "eagle-import") (part "R_0402"))
    )
    (comp (ref "R95")
      (value "100R0")
      (footprint "eagle-import:0402")
      (libsource (lib "eagle-import") (part "R_0402"))
    )
    (comp (ref "R96")
      (value "100R0")
      (footprint "eagle-import:0402")
      (libsource (lib "eagle-import") (part "R_0402"))
    )
    (comp (ref "R100")
      (value "2K2")
      (footprint "eagle-import:0402")
      (libsource (lib "eagle-import") (part "R_0402"))
    )
    (comp (ref "R101")
      (value "100R0")
      (footprint "eagle-import:0402")
      (libsource (lib "eagle-import") (part "R_0402"))
    )
    (comp (ref "R102")
      (value "100R0")
      (footprint "eagle-import:0402")
      (libsource (lib "eagle-import") (part "R_0402"))
    )
    (comp (ref "R106")
      (value "2K2")
      (footprint "eagle-import:0402")
      (libsource (lib "eagle-import") (part "R_0402"))
    )
    (comp (ref "R107")
      (value "100R0")
      (footprint "eagle-import:0402")
      (libsource (lib "eagle-import") (part "R_0402"))
    )
    (comp (ref "R108")
      (value "100R0")
      (footprint "eagle-import:0402")
      (libsource (lib "eagle-import") (part "R_0402"))
    )
    (comp (ref "SW2")
      (value "PTS810SJG250SMTRLFS")
      (footprint "eagle-import:PTS810")
      (fields (field (name "COPYRIGHT") "Copyright (C) 2018 Accelerated Designs. All rights reserved"))
      (libsource (lib "eagle-import") (part "PTS810SJG250SMTRLFS"))
    )
    (comp (ref "SW4")
      (value "PTS810SJG250SMTRLFS")
      (footprint "eagle-import:PTS810")
      (fields (field (name "COPYRIGHT") "Copyright (C) 2018 Accelerated Designs. All rights reserved"))
      (libsource (lib "eagle-import") (part "PTS810SJG250SMTRLFS"))
    )
    (comp (ref "SW6")
      (value "PTS810SJG250SMTRLFS")
      (footprint "eagle-import:PTS810")
      (fields (field (name "COPYRIGHT") "Copyright (C) 2018 Accelerated Designs. All rights reserved"))
      (libsource (lib "eagle-import") (part "PTS810SJG250SMTRLFS"))
    )
    (comp (ref "SW8")
      (value "PTS810SJG250SMTRLFS")
      (footprint "eagle-import:PTS810")
      (fields (field (name "COPYRIGHT") "Copyright (C) 2018 Accelerated Designs. All rights reserved"))
      (libsource (lib "eagle-import") (part "PTS810SJG250SMTRLFS"))
    )
    (comp (ref "SW10")
      (value "PTS810SJG250SMTRLFS")
      (footprint "eagle-import:PTS810")
      (fields (field (name "COPYRIGHT") "Copyright (C) 2018 Accelerated Designs. All rights reserved"))
      (libsource (lib "eagle-import") (part "PTS810SJG250SMTRLFS"))
    )
    (comp (ref "SW12")
      (value "PTS810SJG250SMTRLFS")
      (footprint "eagle-import:PTS810")
      (fields (field (name "COPYRIGHT") "Copyright (C) 2018 Accelerated Designs. All rights reserved"))
      (libsource (lib "eagle-import") (part "PTS810SJG250SMTRLFS"))
    )
    (comp (ref "SW14")
      (value "PTS810SJG250SMTRLFS")
      (footprint "eagle-import:PTS810")
      (fields (field (name "COPYRIGHT") "Copyright (C) 2018 Accelerated Designs. All rights reserved"))
      (libsource (lib "eagle-import") (part "PTS810SJG250SMTRLFS"))
    )
    (comp (ref "SW16")
      (value "PTS810SJG250SMTRLFS")
      (footprint "eagle-import:PTS810")
      (fields (field (name "COPYRIGHT") "Copyright (C) 2018 Accelerated Designs. All rights reserved"))
      (libsource (lib "eagle-import") (part "PTS810SJG250SMTRLFS"))
    )
    (comp (ref "SW18")
      (value "PTS810SJG250SMTRLFS")
      (footprint "eagle-import:PTS810")
      (fields (field (name "COPYRIGHT") "Copyright (C) 2018 Accelerated Designs. All rights reserved"))
      (libsource (lib "eagle-import") (part "PTS810SJG250SMTRLFS"))
    )
    (comp (ref "SW20")
      (value "PTS810SJG250SMTRLFS")
      (footprint "eagle-import:PTS810")
      (fields (field (name "COPYRIGHT") "Copyright (C) 2018 Accelerated Designs. All rights reserved"))
      (libsource (lib "eagle-import") (part "PTS810SJG250SMTRLFS"))
    )
    (comp (ref "U1")
      (value "NPN")
      (footprint "eagle-import:SOT323")
      (fields (field (name "PARTNO") "BC846BW_NPN"))
      (libsource (lib "eagle-import") (part "BC846BW"))
    )
    (comp (ref "U3")
      (value "NPN")
      (footprint "eagle-import:SOT323")
      (fields (field (name "PARTNO") "BC846BW_NPN"))
      (libsource (lib "eagle-import") (part "BC846BW"))
    )
    (comp (ref "U5")
      (value "NPN")
      (footprint "eagle-import:SOT323")
      (fields (field (name "PARTNO") "BC846BW_NPN"))
      (libsource (lib "eagle-import") (part "BC846BW"))
    )
    (comp (ref "U7")
      (value "NPN")
      (footprint "eagle-import:SOT323")
      (fields (field (name "PARTNO") "BC846BW_NPN"))
      (libsource (lib "eagle-import") (part "BC846BW"))
    )
    (comp (ref "U9")
      (value "NPN")
      (footprint "eagle-import:SOT323")
      (fields (field (name "PARTNO") "BC846BW_NPN"))
      (libsource (lib "eagle-import") (part "BC846BW"))
    )
    (comp (ref "U11")
      (value "NPN")
      (footprint "eagle-import:SOT323")
      (fields (field (name "PARTNO") "BC846BW_NPN"))
      (libsource (lib "eagle-import") (part "BC846BW"))
    )
    (comp (ref "U13")
      (value "NPN")
      (footprint "eagle-import:SOT323")
      (fields (field (name "PARTNO") "BC846BW_NPN"))
      (libsource (lib "eagle-import") (part "BC846BW"))
    )
    (comp (ref "U15")
      (value "NPN")
      (footprint "eagle-import:SOT323")
      (fields (field (name "PARTNO") "BC846BW_NPN"))
      (libsource (lib "eagle-import") (part "BC846BW"))
    )
    (comp (ref "U17")
      (value "NPN")
      (footprint "eagle-import:SOT323")
      (fields (field (name "PARTNO") "BC846BW_NPN"))
      (libsource (lib "eagle-import") (part "BC846BW"))
    )
    (comp (ref "U20")
      (value "NPN")
      (footprint "eagle-import:SOT323")
      (fields (field (name "PARTNO") "BC846BW_NPN"))
      (libsource (lib "eagle-import") (part "BC846BW"))
    )
  )
  (nets
    (net (code "1") (name "A_DIR+_A") (class "Default")
      (node (ref "J14") (pin "3") (pinfunction "3-DIR+_3") (pintype "passive"))
      (node (ref "R54") (pin "2") (pinfunction "2_2") (pintype "passive"))
    )
    (net (code "2") (name "A_DIR+_C") (class "Default")
      (node (ref "J18") (pin "3") (pinfunction "3-DIR+_3") (pintype "passive"))
      (node (ref "R70") (pin "2") (pinfunction "2_2") (pintype "passive"))
    )
    (net (code "3") (name "A_DIR+_WF") (class "Default")
      (node (ref "J4") (pin "3") (pinfunction "3-DIR+_3") (pintype "passive"))
      (node (ref "R14") (pin "2") (pinfunction "2_2") (pintype "passive"))
    )
    (net (code "4") (name "A_DIR+_X") (class "Default")
      (node (ref "J2") (pin "3") (pinfunction "3-DIR+_3") (pintype "passive"))
      (node (ref "R6") (pin "2") (pinfunction "2_2") (pintype "passive"))
    )
    (net (code "5") (name "A_DIR+_Y") (class "Default")
      (node (ref "J6") (pin "3") (pinfunction "3-DIR+_3") (pintype "passive"))
      (node (ref "R22") (pin "2") (pinfunction "2_2") (pintype "passive"))
    )
    (net (code "6") (name "A_DIR+_Z") (class "Default")
      (node (ref "J10") (pin "3") (pinfunction "3-DIR+_3") (pintype "passive"))
      (node (ref "R38") (pin "2") (pinfunction "2_2") (pintype "passive"))
    )
    (net (code "7") (name "A_DIR-A") (class "Default")
      (node (ref "J14") (pin "7") (pinfunction "7-DIR-_7") (pintype "passive"))
      (node (ref "LED54") (pin "2") (pinfunction "C_2") (pintype "passive"))
    )
    (net (code "8") (name "A_DIR-C") (class "Default")
      (node (ref "J18") (pin "7") (pinfunction "7-DIR-_7") (pintype "passive"))
      (node (ref "LED70") (pin "2") (pinfunction "C_2") (pintype "passive"))
    )
    (net (code "9") (name "A_DIR-X") (class "Default")
      (node (ref "J2") (pin "7") (pinfunction "7-DIR-_7") (pintype "passive"))
      (node (ref "LED6") (pin "2") (pinfunction "C_2") (pintype "passive"))
    )
    (net (code "10") (name "A_DIR-Y") (class "Default")
      (node (ref "J6") (pin "7") (pinfunction "7-DIR-_7") (pintype "passive"))
      (node (ref "LED22") (pin "2") (pinfunction "C_2") (pintype "passive"))
    )
    (net (code "11") (name "A_DIR-Z") (class "Default")
      (node (ref "J10") (pin "7") (pinfunction "7-DIR-_7") (pintype "passive"))
      (node (ref "LED38") (pin "2") (pinfunction "C_2") (pintype "passive"))
    )
    (net (code "12") (name "A_DIR-_WF") (class "Default")
      (node (ref "J4") (pin "7") (pinfunction "7-DIR-_7") (pintype "passive"))
      (node (ref "LED14") (pin "2") (pinfunction "C_2") (pintype "passive"))
    )
    (net (code "13") (name "A_ENABLE+_A") (class "Default")
      (node (ref "J14") (pin "4") (pinfunction "4-ENABLE+_4") (pintype "passive"))
      (node (ref "R55") (pin "2") (pinfunction "2_2") (pintype "passive"))
    )
    (net (code "14") (name "A_ENABLE+_C") (class "Default")
      (node (ref "J18") (pin "4") (pinfunction "4-ENABLE+_4") (pintype "passive"))
      (node (ref "R71") (pin "2") (pinfunction "2_2") (pintype "passive"))
    )
    (net (code "15") (name "A_ENABLE+_WF") (class "Default")
      (node (ref "J4") (pin "4") (pinfunction "4-ENABLE+_4") (pintype "passive"))
      (node (ref "R15") (pin "2") (pinfunction "2_2") (pintype "passive"))
    )
    (net (code "16") (name "A_ENABLE+_X") (class "Default")
      (node (ref "J2") (pin "4") (pinfunction "4-ENABLE+_4") (pintype "passive"))
      (node (ref "R7") (pin "2") (pinfunction "2_2") (pintype "passive"))
    )
    (net (code "17") (name "A_ENABLE+_Y") (class "Default")
      (node (ref "J6") (pin "4") (pinfunction "4-ENABLE+_4") (pintype "passive"))
      (node (ref "R23") (pin "2") (pinfunction "2_2") (pintype "passive"))
    )
    (net (code "18") (name "A_ENABLE+_Z") (class "Default")
      (node (ref "J10") (pin "4") (pinfunction "4-ENABLE+_4") (pintype "passive"))
      (node (ref "R39") (pin "2") (pinfunction "2_2") (pintype "passive"))
    )
    (net (code "19") (name "A_ENABLE-_A") (class "Default")
      (node (ref "J14") (pin "8") (pinfunction "8-ENABLE-_8") (pintype "passive"))
      (node (ref "LED55") (pin "2") (pinfunction "C_2") (pintype "passive"))
    )
    (net (code "20") (name "A_ENABLE-_C") (class "Default")
      (node (ref "J18") (pin "8") (pinfunction "8-ENABLE-_8") (pintype "passive"))
      (node (ref "LED71") (pin "2") (pinfunction "C_2") (pintype "passive"))
    )
    (net (code "21") (name "A_ENABLE-_WF") (class "Default")
      (node (ref "J4") (pin "8") (pinfunction "8-ENABLE-_8") (pintype "passive"))
      (node (ref "LED15") (pin "2") (pinfunction "C_2") (pintype "passive"))
    )
    (net (code "22") (name "A_ENABLE-_X") (class "Default")
      (node (ref "J2") (pin "8") (pinfunction "8-ENABLE-_8") (pintype "passive"))
      (node (ref "LED7") (pin "2") (pinfunction "C_2") (pintype "passive"))
    )
    (net (code "23") (name "A_ENABLE-_Y") (class "Default")
      (node (ref "J6") (pin "8") (pinfunction "8-ENABLE-_8") (pintype "passive"))
      (node (ref "LED23") (pin "2") (pinfunction "C_2") (pintype "passive"))
    )
    (net (code "24") (name "A_ENABLE-_Z") (class "Default")
      (node (ref "J10") (pin "8") (pinfunction "8-ENABLE-_8") (pintype "passive"))
      (node (ref "LED39") (pin "2") (pinfunction "C_2") (pintype "passive"))
    )
    (net (code "25") (name "A_HLFB+_A") (class "Default")
      (node (ref "J14") (pin "1") (pinfunction "1-HLFB+_1") (pintype "passive"))
      (node (ref "R56") (pin "2") (pinfunction "2_2") (pintype "passive"))
    )
    (net (code "26") (name "A_HLFB+_C") (class "Default")
      (node (ref "J18") (pin "1") (pinfunction "1-HLFB+_1") (pintype "passive"))
      (node (ref "R72") (pin "2") (pinfunction "2_2") (pintype "passive"))
    )
    (net (code "27") (name "A_HLFB+_WF") (class "Default")
      (node (ref "J4") (pin "1") (pinfunction "1-HLFB+_1") (pintype "passive"))
      (node (ref "R16") (pin "2") (pinfunction "2_2") (pintype "passive"))
    )
    (net (code "28") (name "A_HLFB+_X") (class "Default")
      (node (ref "J2") (pin "1") (pinfunction "1-HLFB+_1") (pintype "passive"))
      (node (ref "R8") (pin "2") (pinfunction "2_2") (pintype "passive"))
    )
    (net (code "29") (name "A_HLFB+_Y") (class "Default")
      (node (ref "J6") (pin "1") (pinfunction "1-HLFB+_1") (pintype "passive"))
      (node (ref "R24") (pin "2") (pinfunction "2_2") (pintype "passive"))
    )
    (net (code "30") (name "A_HLFB+_Z") (class "Default")
      (node (ref "J10") (pin "1") (pinfunction "1-HLFB+_1") (pintype "passive"))
      (node (ref "R40") (pin "2") (pinfunction "2_2") (pintype "passive"))
    )
    (net (code "31") (name "A_HLFB-_A") (class "Default")
      (node (ref "J14") (pin "5") (pinfunction "5-HLFB-_5") (pintype "passive"))
      (node (ref "LED56") (pin "2") (pinfunction "C_2") (pintype "passive"))
    )
    (net (code "32") (name "A_HLFB-_C") (class "Default")
      (node (ref "J18") (pin "5") (pinfunction "5-HLFB-_5") (pintype "passive"))
      (node (ref "LED72") (pin "2") (pinfunction "C_2") (pintype "passive"))
    )
    (net (code "33") (name "A_HLFB-_WF") (class "Default")
      (node (ref "J4") (pin "5") (pinfunction "5-HLFB-_5") (pintype "passive"))
      (node (ref "LED16") (pin "2") (pinfunction "C_2") (pintype "passive"))
    )
    (net (code "34") (name "A_HLFB-_X") (class "Default")
      (node (ref "J2") (pin "5") (pinfunction "5-HLFB-_5") (pintype "passive"))
      (node (ref "LED8") (pin "2") (pinfunction "C_2") (pintype "passive"))
    )
    (net (code "35") (name "A_HLFB-_Y") (class "Default")
      (node (ref "J6") (pin "5") (pinfunction "5-HLFB-_5") (pintype "passive"))
      (node (ref "LED24") (pin "2") (pinfunction "C_2") (pintype "passive"))
    )
    (net (code "36") (name "A_HLFB-_Z") (class "Default")
      (node (ref "J10") (pin "5") (pinfunction "5-HLFB-_5") (pintype "passive"))
      (node (ref "LED40") (pin "2") (pinfunction "C_2") (pintype "passive"))
    )
    (net (code "37") (name "A_STEP+_A") (class "Default")
      (node (ref "J14") (pin "2") (pinfunction "2-STEP+_2") (pintype "passive"))
      (node (ref "R53") (pin "2") (pinfunction "2_2") (pintype "passive"))
    )
    (net (code "38") (name "A_STEP+_C") (class "Default")
      (node (ref "J18") (pin "2") (pinfunction "2-STEP+_2") (pintype "passive"))
      (node (ref "R69") (pin "2") (pinfunction "2_2") (pintype "passive"))
    )
    (net (code "39") (name "A_STEP+_WF") (class "Default")
      (node (ref "J4") (pin "2") (pinfunction "2-STEP+_2") (pintype "passive"))
      (node (ref "R13") (pin "2") (pinfunction "2_2") (pintype "passive"))
    )
    (net (code "40") (name "A_STEP+_X") (class "Default")
      (node (ref "J2") (pin "2") (pinfunction "2-STEP+_2") (pintype "passive"))
      (node (ref "R5") (pin "2") (pinfunction "2_2") (pintype "passive"))
    )
    (net (code "41") (name "A_STEP+_Y") (class "Default")
      (node (ref "J6") (pin "2") (pinfunction "2-STEP+_2") (pintype "passive"))
      (node (ref "R21") (pin "2") (pinfunction "2_2") (pintype "passive"))
    )
    (net (code "42") (name "A_STEP+_Z") (class "Default")
      (node (ref "J10") (pin "2") (pinfunction "2-STEP+_2") (pintype "passive"))
      (node (ref "R37") (pin "2") (pinfunction "2_2") (pintype "passive"))
    )
    (net (code "43") (name "A_STEP-_A") (class "Default")
      (node (ref "J14") (pin "6") (pinfunction "6-STEP-_6") (pintype "passive"))
      (node (ref "LED53") (pin "2") (pinfunction "C_2") (pintype "passive"))
    )
    (net (code "44") (name "A_STEP-_C") (class "Default")
      (node (ref "J18") (pin "6") (pinfunction "6-STEP-_6") (pintype "passive"))
      (node (ref "LED69") (pin "2") (pinfunction "C_2") (pintype "passive"))
    )
    (net (code "45") (name "A_STEP-_WF") (class "Default")
      (node (ref "J4") (pin "6") (pinfunction "6-STEP-_6") (pintype "passive"))
      (node (ref "LED13") (pin "2") (pinfunction "C_2") (pintype "passive"))
    )
    (net (code "46") (name "A_STEP-_X") (class "Default")
      (node (ref "J2") (pin "6") (pinfunction "6-STEP-_6") (pintype "passive"))
      (node (ref "LED5") (pin "2") (pinfunction "C_2") (pintype "passive"))
    )
    (net (code "47") (name "A_STEP-_Y") (class "Default")
      (node (ref "J6") (pin "6") (pinfunction "6-STEP-_6") (pintype "passive"))
      (node (ref "LED21") (pin "2") (pinfunction "C_2") (pintype "passive"))
    )
    (net (code "48") (name "A_STEP-_Z") (class "Default")
      (node (ref "J10") (pin "6") (pinfunction "6-STEP-_6") (pintype "passive"))
      (node (ref "LED37") (pin "2") (pinfunction "C_2") (pintype "passive"))
    )
    (net (code "49") (name "BLACK_1") (class "Default")
      (node (ref "J11") (pin "1") (pinfunction "1_1") (pintype "passive"))
      (node (ref "J12") (pin "P$1") (pinfunction "P$1_P$1") (pintype "bidirectional"))
      (node (ref "R28") (pin "P$1") (pinfunction "1_P$1") (pintype "passive"))
      (node (ref "R29") (pin "P$1") (pinfunction "1_P$1") (pintype "passive"))
    )
    (net (code "50") (name "BLACK_2") (class "Default")
      (node (ref "J19") (pin "1") (pinfunction "1_1") (pintype "passive"))
      (node (ref "J20") (pin "P$1") (pinfunction "P$1_P$1") (pintype "bidirectional"))
      (node (ref "R42") (pin "P$1") (pinfunction "1_P$1") (pintype "passive"))
      (node (ref "R43") (pin "P$1") (pinfunction "1_P$1") (pintype "passive"))
    )
    (net (code "51") (name "BLACK_3") (class "Default")
      (node (ref "J23") (pin "1") (pinfunction "1_1") (pintype "passive"))
      (node (ref "J24") (pin "P$1") (pinfunction "P$1_P$1") (pintype "bidirectional"))
      (node (ref "R48") (pin "P$1") (pinfunction "1_P$1") (pintype "passive"))
      (node (ref "R57") (pin "P$1") (pinfunction "1_P$1") (pintype "passive"))
    )
    (net (code "52") (name "BLACK_4") (class "Default")
      (node (ref "J27") (pin "1") (pinfunction "1_1") (pintype "passive"))
      (node (ref "J28") (pin "P$1") (pinfunction "P$1_P$1") (pintype "bidirectional"))
      (node (ref "R63") (pin "P$1") (pinfunction "1_P$1") (pintype "passive"))
      (node (ref "R64") (pin "P$1") (pinfunction "1_P$1") (pintype "passive"))
    )
    (net (code "53") (name "BLACK_5") (class "Default")
      (node (ref "J31") (pin "1") (pinfunction "1_1") (pintype "passive"))
      (node (ref "J32") (pin "P$1") (pinfunction "P$1_P$1") (pintype "bidirectional"))
      (node (ref "R77") (pin "P$1") (pinfunction "1_P$1") (pintype "passive"))
      (node (ref "R78") (pin "P$1") (pinfunction "1_P$1") (pintype "passive"))
    )
    (net (code "54") (name "BLACK_6") (class "Default")
      (node (ref "J35") (pin "1") (pinfunction "1_1") (pintype "passive"))
      (node (ref "J36") (pin "P$1") (pinfunction "P$1_P$1") (pintype "bidirectional"))
      (node (ref "R83") (pin "P$1") (pinfunction "1_P$1") (pintype "passive"))
      (node (ref "R84") (pin "P$1") (pinfunction "1_P$1") (pintype "passive"))
    )
    (net (code "55") (name "BLACK_7") (class "Default")
      (node (ref "J39") (pin "1") (pinfunction "1_1") (pintype "passive"))
      (node (ref "J40") (pin "P$1") (pinfunction "P$1_P$1") (pintype "bidirectional"))
      (node (ref "R89") (pin "P$1") (pinfunction "1_P$1") (pintype "passive"))
      (node (ref "R90") (pin "P$1") (pinfunction "1_P$1") (pintype "passive"))
    )
    (net (code "56") (name "BLACK_8") (class "Default")
      (node (ref "J43") (pin "1") (pinfunction "1_1") (pintype "passive"))
      (node (ref "J44") (pin "P$1") (pinfunction "P$1_P$1") (pintype "bidirectional"))
      (node (ref "R95") (pin "P$1") (pinfunction "1_P$1") (pintype "passive"))
      (node (ref "R96") (pin "P$1") (pinfunction "1_P$1") (pintype "passive"))
    )
    (net (code "57") (name "BLACK_9") (class "Default")
      (node (ref "J47") (pin "1") (pinfunction "1_1") (pintype "passive"))
      (node (ref "J48") (pin "P$1") (pinfunction "P$1_P$1") (pintype "bidirectional"))
      (node (ref "R101") (pin "P$1") (pinfunction "1_P$1") (pintype "passive"))
      (node (ref "R102") (pin "P$1") (pinfunction "1_P$1") (pintype "passive"))
    )
    (net (code "58") (name "BLACK_E_STOP") (class "Default")
      (node (ref "J51") (pin "1") (pinfunction "1_1") (pintype "passive"))
      (node (ref "J52") (pin "P$1") (pinfunction "P$1_P$1") (pintype "bidirectional"))
      (node (ref "R107") (pin "P$1") (pinfunction "1_P$1") (pintype "passive"))
      (node (ref "R108") (pin "P$1") (pinfunction "1_P$1") (pintype "passive"))
    )
    (net (code "59") (name "BLUE") (class "Default")
      (node (ref "J11") (pin "2") (pinfunction "2_2") (pintype "passive"))
      (node (ref "J12") (pin "P$2") (pinfunction "P$2_P$2") (pintype "bidirectional"))
      (node (ref "J12") (pin "P$3") (pinfunction "P$3_P$3") (pintype "bidirectional"))
      (node (ref "J19") (pin "2") (pinfunction "2_2") (pintype "passive"))
      (node (ref "J20") (pin "P$2") (pinfunction "P$2_P$2") (pintype "bidirectional"))
      (node (ref "J20") (pin "P$3") (pinfunction "P$3_P$3") (pintype "bidirectional"))
      (node (ref "J23") (pin "2") (pinfunction "2_2") (pintype "passive"))
      (node (ref "J24") (pin "P$2") (pinfunction "P$2_P$2") (pintype "bidirectional"))
      (node (ref "J24") (pin "P$3") (pinfunction "P$3_P$3") (pintype "bidirectional"))
      (node (ref "J27") (pin "2") (pinfunction "2_2") (pintype "passive"))
      (node (ref "J28") (pin "P$2") (pinfunction "P$2_P$2") (pintype "bidirectional"))
      (node (ref "J28") (pin "P$3") (pinfunction "P$3_P$3") (pintype "bidirectional"))
      (node (ref "J35") (pin "2") (pinfunction "2_2") (pintype "passive"))
      (node (ref "J36") (pin "P$2") (pinfunction "P$2_P$2") (pintype "bidirectional"))
      (node (ref "J36") (pin "P$3") (pinfunction "P$3_P$3") (pintype "bidirectional"))
      (node (ref "J39") (pin "2") (pinfunction "2_2") (pintype "passive"))
      (node (ref "J40") (pin "P$2") (pinfunction "P$2_P$2") (pintype "bidirectional"))
      (node (ref "J40") (pin "P$3") (pinfunction "P$3_P$3") (pintype "bidirectional"))
      (node (ref "J43") (pin "2") (pinfunction "2_2") (pintype "passive"))
      (node (ref "J44") (pin "P$2") (pinfunction "P$2_P$2") (pintype "bidirectional"))
      (node (ref "J44") (pin "P$3") (pinfunction "P$3_P$3") (pintype "bidirectional"))
      (node (ref "J47") (pin "2") (pinfunction "2_2") (pintype "passive"))
      (node (ref "J48") (pin "P$2") (pinfunction "P$2_P$2") (pintype "bidirectional"))
      (node (ref "J48") (pin "P$3") (pinfunction "P$3_P$3") (pintype "bidirectional"))
      (node (ref "J51") (pin "2") (pinfunction "2_2") (pintype "passive"))
      (node (ref "J52") (pin "P$2") (pinfunction "P$2_P$2") (pintype "bidirectional"))
      (node (ref "J52") (pin "P$3") (pinfunction "P$3_P$3") (pintype "bidirectional"))
      (node (ref "SW10") (pin "3") (pinfunction "3_3") (pintype "passive"))
      (node (ref "SW10") (pin "4") (pinfunction "4_4") (pintype "passive"))
      (node (ref "SW12") (pin "3") (pinfunction "3_3") (pintype "passive"))
      (node (ref "SW12") (pin "4") (pinfunction "4_4") (pintype "passive"))
      (node (ref "SW14") (pin "3") (pinfunction "3_3") (pintype "passive"))
      (node (ref "SW14") (pin "4") (pinfunction "4_4") (pintype "passive"))
      (node (ref "SW16") (pin "3") (pinfunction "3_3") (pintype "passive"))
      (node (ref "SW16") (pin "4") (pinfunction "4_4") (pintype "passive"))
      (node (ref "SW18") (pin "3") (pinfunction "3_3") (pintype "passive"))
      (node (ref "SW18") (pin "4") (pinfunction "4_4") (pintype "passive"))
      (node (ref "SW2") (pin "3") (pinfunction "3_3") (pintype "passive"))
      (node (ref "SW2") (pin "4") (pinfunction "4_4") (pintype "passive"))
      (node (ref "SW20") (pin "3") (pinfunction "3_3") (pintype "passive"))
      (node (ref "SW20") (pin "4") (pinfunction "4_4") (pintype "passive"))
      (node (ref "SW4") (pin "3") (pinfunction "3_3") (pintype "passive"))
      (node (ref "SW4") (pin "4") (pinfunction "4_4") (pintype "passive"))
      (node (ref "SW6") (pin "3") (pinfunction "3_3") (pintype "passive"))
      (node (ref "SW6") (pin "4") (pinfunction "4_4") (pintype "passive"))
      (node (ref "SW8") (pin "3") (pinfunction "3_3") (pintype "passive"))
      (node (ref "SW8") (pin "4") (pinfunction "4_4") (pintype "passive"))
    )
    (net (code "60") (name "BROWN") (class "Default")
      (node (ref "J11") (pin "3") (pinfunction "3_3") (pintype "passive"))
      (node (ref "J12") (pin "P$4") (pinfunction "P$4_P$4") (pintype "bidirectional"))
      (node (ref "J19") (pin "3") (pinfunction "3_3") (pintype "passive"))
      (node (ref "J20") (pin "P$4") (pinfunction "P$4_P$4") (pintype "bidirectional"))
      (node (ref "J23") (pin "3") (pinfunction "3_3") (pintype "passive"))
      (node (ref "J24") (pin "P$4") (pinfunction "P$4_P$4") (pintype "bidirectional"))
      (node (ref "J27") (pin "3") (pinfunction "3_3") (pintype "passive"))
      (node (ref "J28") (pin "P$4") (pinfunction "P$4_P$4") (pintype "bidirectional"))
      (node (ref "J31") (pin "3") (pinfunction "3_3") (pintype "passive"))
      (node (ref "J32") (pin "P$4") (pinfunction "P$4_P$4") (pintype "bidirectional"))
      (node (ref "J35") (pin "3") (pinfunction "3_3") (pintype "passive"))
      (node (ref "J36") (pin "P$4") (pinfunction "P$4_P$4") (pintype "bidirectional"))
      (node (ref "J39") (pin "3") (pinfunction "3_3") (pintype "passive"))
      (node (ref "J40") (pin "P$4") (pinfunction "P$4_P$4") (pintype "bidirectional"))
      (node (ref "J43") (pin "3") (pinfunction "3_3") (pintype "passive"))
      (node (ref "J44") (pin "P$4") (pinfunction "P$4_P$4") (pintype "bidirectional"))
      (node (ref "J47") (pin "3") (pinfunction "3_3") (pintype "passive"))
      (node (ref "J48") (pin "P$4") (pinfunction "P$4_P$4") (pintype "bidirectional"))
      (node (ref "J51") (pin "3") (pinfunction "3_3") (pintype "passive"))
      (node (ref "J52") (pin "P$4") (pinfunction "P$4_P$4") (pintype "bidirectional"))
      (node (ref "R100") (pin "P$1") (pinfunction "1_P$1") (pintype "passive"))
      (node (ref "R106") (pin "P$1") (pinfunction "1_P$1") (pintype "passive"))
      (node (ref "R27") (pin "P$1") (pinfunction "1_P$1") (pintype "passive"))
      (node (ref "R41") (pin "P$1") (pinfunction "1_P$1") (pintype "passive"))
      (node (ref "R47") (pin "P$1") (pinfunction "1_P$1") (pintype "passive"))
      (node (ref "R62") (pin "P$1") (pinfunction "1_P$1") (pintype "passive"))
      (node (ref "R76") (pin "P$1") (pinfunction "1_P$1") (pintype "passive"))
      (node (ref "R82") (pin "P$1") (pinfunction "1_P$1") (pintype "passive"))
      (node (ref "R88") (pin "P$1") (pinfunction "1_P$1") (pintype "passive"))
      (node (ref "R94") (pin "P$1") (pinfunction "1_P$1") (pintype "passive"))
      (node (ref "U1") (pin "3") (pinfunction "C(3)_3") (pintype "input"))
      (node (ref "U11") (pin "3") (pinfunction "C(3)_3") (pintype "input"))
      (node (ref "U13") (pin "3") (pinfunction "C(3)_3") (pintype "input"))
      (node (ref "U15") (pin "3") (pinfunction "C(3)_3") (pintype "input"))
      (node (ref "U17") (pin "3") (pinfunction "C(3)_3") (pintype "input"))
      (node (ref "U20") (pin "3") (pinfunction "C(3)_3") (pintype "input"))
      (node (ref "U3") (pin "3") (pinfunction "C(3)_3") (pintype "input"))
      (node (ref "U5") (pin "3") (pinfunction "C(3)_3") (pintype "input"))
      (node (ref "U7") (pin "3") (pinfunction "C(3)_3") (pintype "input"))
      (node (ref "U9") (pin "3") (pinfunction "C(3)_3") (pintype "input"))
    )
    (net (code "61") (name "B_DIR+_A") (class "Default")
      (node (ref "J13") (pin "3") (pinfunction "3-DIR+_3") (pintype "passive"))
      (node (ref "R50") (pin "2") (pinfunction "2_2") (pintype "passive"))
    )
    (net (code "62") (name "B_DIR+_C") (class "Default")
      (node (ref "J1") (pin "3") (pinfunction "3-DIR+_3") (pintype "passive"))
      (node (ref "R2") (pin "2") (pinfunction "2_2") (pintype "passive"))
    )
    (net (code "63") (name "B_DIR+_WF") (class "Default")
      (node (ref "J17") (pin "3") (pinfunction "3-DIR+_3") (pintype "passive"))
      (node (ref "R66") (pin "2") (pinfunction "2_2") (pintype "passive"))
    )
    (net (code "64") (name "B_DIR+_X") (class "Default")
      (node (ref "J3") (pin "3") (pinfunction "3-DIR+_3") (pintype "passive"))
      (node (ref "R10") (pin "2") (pinfunction "2_2") (pintype "passive"))
    )
    (net (code "65") (name "B_DIR+_Y") (class "Default")
      (node (ref "J5") (pin "3") (pinfunction "3-DIR+_3") (pintype "passive"))
      (node (ref "R18") (pin "2") (pinfunction "2_2") (pintype "passive"))
    )
    (net (code "66") (name "B_DIR+_Z") (class "Default")
      (node (ref "J9") (pin "3") (pinfunction "3-DIR+_3") (pintype "passive"))
      (node (ref "R34") (pin "2") (pinfunction "2_2") (pintype "passive"))
    )
    (net (code "67") (name "B_DIR-C") (class "Default")
      (node (ref "J1") (pin "7") (pinfunction "7-DIR-_7") (pintype "passive"))
      (node (ref "LED2") (pin "2") (pinfunction "C_2") (pintype "passive"))
    )
    (net (code "68") (name "B_DIR-X") (class "Default")
      (node (ref "J3") (pin "7") (pinfunction "7-DIR-_7") (pintype "passive"))
      (node (ref "LED10") (pin "2") (pinfunction "C_2") (pintype "passive"))
    )
    (net (code "69") (name "B_DIR-Y") (class "Default")
      (node (ref "J5") (pin "7") (pinfunction "7-DIR-_7") (pintype "passive"))
      (node (ref "LED18") (pin "2") (pinfunction "C_2") (pintype "passive"))
    )
    (net (code "70") (name "B_DIR-Z") (class "Default")
      (node (ref "J9") (pin "7") (pinfunction "7-DIR-_7") (pintype "passive"))
      (node (ref "LED34") (pin "2") (pinfunction "C_2") (pintype "passive"))
    )
    (net (code "71") (name "B_DIR-_A") (class "Default")
      (node (ref "J13") (pin "7") (pinfunction "7-DIR-_7") (pintype "passive"))
      (node (ref "LED50") (pin "2") (pinfunction "C_2") (pintype "passive"))
    )
    (net (code "72") (name "B_DIR-_WF") (class "Default")
      (node (ref "J17") (pin "7") (pinfunction "7-DIR-_7") (pintype "passive"))
      (node (ref "LED66") (pin "2") (pinfunction "C_2") (pintype "passive"))
    )
    (net (code "73") (name "B_ENABLE+_A") (class "Default")
      (node (ref "J13") (pin "4") (pinfunction "4-ENABLE+_4") (pintype "passive"))
      (node (ref "R51") (pin "2") (pinfunction "2_2") (pintype "passive"))
    )
    (net (code "74") (name "B_ENABLE+_C") (class "Default")
      (node (ref "J1") (pin "4") (pinfunction "4-ENABLE+_4") (pintype "passive"))
      (node (ref "R3") (pin "2") (pinfunction "2_2") (pintype "passive"))
    )
    (net (code "75") (name "B_ENABLE+_WF") (class "Default")
      (node (ref "J17") (pin "4") (pinfunction "4-ENABLE+_4") (pintype "passive"))
      (node (ref "R67") (pin "2") (pinfunction "2_2") (pintype "passive"))
    )
    (net (code "76") (name "B_ENABLE+_X") (class "Default")
      (node (ref "J3") (pin "4") (pinfunction "4-ENABLE+_4") (pintype "passive"))
      (node (ref "R11") (pin "2") (pinfunction "2_2") (pintype "passive"))
    )
    (net (code "77") (name "B_ENABLE+_Y") (class "Default")
      (node (ref "J5") (pin "4") (pinfunction "4-ENABLE+_4") (pintype "passive"))
      (node (ref "R19") (pin "2") (pinfunction "2_2") (pintype "passive"))
    )
    (net (code "78") (name "B_ENABLE+_Z") (class "Default")
      (node (ref "J9") (pin "4") (pinfunction "4-ENABLE+_4") (pintype "passive"))
      (node (ref "R35") (pin "2") (pinfunction "2_2") (pintype "passive"))
    )
    (net (code "79") (name "B_ENABLE-_A") (class "Default")
      (node (ref "J13") (pin "8") (pinfunction "8-ENABLE-_8") (pintype "passive"))
      (node (ref "LED51") (pin "2") (pinfunction "C_2") (pintype "passive"))
    )
    (net (code "80") (name "B_ENABLE-_C") (class "Default")
      (node (ref "J1") (pin "8") (pinfunction "8-ENABLE-_8") (pintype "passive"))
      (node (ref "LED3") (pin "2") (pinfunction "C_2") (pintype "passive"))
    )
    (net (code "81") (name "B_ENABLE-_WF") (class "Default")
      (node (ref "J17") (pin "8") (pinfunction "8-ENABLE-_8") (pintype "passive"))
      (node (ref "LED67") (pin "2") (pinfunction "C_2") (pintype "passive"))
    )
    (net (code "82") (name "B_ENABLE-_X") (class "Default")
      (node (ref "J3") (pin "8") (pinfunction "8-ENABLE-_8") (pintype "passive"))
      (node (ref "LED11") (pin "2") (pinfunction "C_2") (pintype "passive"))
    )
    (net (code "83") (name "B_ENABLE-_Y") (class "Default")
      (node (ref "J5") (pin "8") (pinfunction "8-ENABLE-_8") (pintype "passive"))
      (node (ref "LED19") (pin "2") (pinfunction "C_2") (pintype "passive"))
    )
    (net (code "84") (name "B_ENABLE-_Z") (class "Default")
      (node (ref "J9") (pin "8") (pinfunction "8-ENABLE-_8") (pintype "passive"))
      (node (ref "LED35") (pin "2") (pinfunction "C_2") (pintype "passive"))
    )
    (net (code "85") (name "B_HLFB+_A") (class "Default")
      (node (ref "J13") (pin "1") (pinfunction "1-HLFB+_1") (pintype "passive"))
      (node (ref "R52") (pin "2") (pinfunction "2_2") (pintype "passive"))
    )
    (net (code "86") (name "B_HLFB+_C") (class "Default")
      (node (ref "J1") (pin "1") (pinfunction "1-HLFB+_1") (pintype "passive"))
      (node (ref "R4") (pin "2") (pinfunction "2_2") (pintype "passive"))
    )
    (net (code "87") (name "B_HLFB+_WF") (class "Default")
      (node (ref "J17") (pin "1") (pinfunction "1-HLFB+_1") (pintype "passive"))
      (node (ref "R68") (pin "2") (pinfunction "2_2") (pintype "passive"))
    )
    (net (code "88") (name "B_HLFB+_X") (class "Default")
      (node (ref "J3") (pin "1") (pinfunction "1-HLFB+_1") (pintype "passive"))
      (node (ref "R12") (pin "2") (pinfunction "2_2") (pintype "passive"))
    )
    (net (code "89") (name "B_HLFB+_Y") (class "Default")
      (node (ref "J5") (pin "1") (pinfunction "1-HLFB+_1") (pintype "passive"))
      (node (ref "R20") (pin "2") (pinfunction "2_2") (pintype "passive"))
    )
    (net (code "90") (name "B_HLFB+_Z") (class "Default")
      (node (ref "J9") (pin "1") (pinfunction "1-HLFB+_1") (pintype "passive"))
      (node (ref "R36") (pin "2") (pinfunction "2_2") (pintype "passive"))
    )
    (net (code "91") (name "B_HLFB-_A") (class "Default")
      (node (ref "J13") (pin "5") (pinfunction "5-HLFB-_5") (pintype "passive"))
      (node (ref "LED52") (pin "2") (pinfunction "C_2") (pintype "passive"))
    )
    (net (code "92") (name "B_HLFB-_C") (class "Default")
      (node (ref "J1") (pin "5") (pinfunction "5-HLFB-_5") (pintype "passive"))
      (node (ref "LED4") (pin "2") (pinfunction "C_2") (pintype "passive"))
    )
    (net (code "93") (name "B_HLFB-_WF") (class "Default")
      (node (ref "J17") (pin "5") (pinfunction "5-HLFB-_5") (pintype "passive"))
      (node (ref "LED68") (pin "2") (pinfunction "C_2") (pintype "passive"))
    )
    (net (code "94") (name "B_HLFB-_X") (class "Default")
      (node (ref "J3") (pin "5") (pinfunction "5-HLFB-_5") (pintype "passive"))
      (node (ref "LED12") (pin "2") (pinfunction "C_2") (pintype "passive"))
    )
    (net (code "95") (name "B_HLFB-_Y") (class "Default")
      (node (ref "J5") (pin "5") (pinfunction "5-HLFB-_5") (pintype "passive"))
      (node (ref "LED20") (pin "2") (pinfunction "C_2") (pintype "passive"))
    )
    (net (code "96") (name "B_HLFB-_Z") (class "Default")
      (node (ref "J9") (pin "5") (pinfunction "5-HLFB-_5") (pintype "passive"))
      (node (ref "LED36") (pin "2") (pinfunction "C_2") (pintype "passive"))
    )
    (net (code "97") (name "B_STEP+_A") (class "Default")
      (node (ref "J13") (pin "2") (pinfunction "2-STEP+_2") (pintype "passive"))
      (node (ref "R49") (pin "2") (pinfunction "2_2") (pintype "passive"))
    )
    (net (code "98") (name "B_STEP+_C") (class "Default")
      (node (ref "J1") (pin "2") (pinfunction "2-STEP+_2") (pintype "passive"))
      (node (ref "R1") (pin "2") (pinfunction "2_2") (pintype "passive"))
    )
    (net (code "99") (name "B_STEP+_WF") (class "Default")
      (node (ref "J17") (pin "2") (pinfunction "2-STEP+_2") (pintype "passive"))
      (node (ref "R65") (pin "2") (pinfunction "2_2") (pintype "passive"))
    )
    (net (code "100") (name "B_STEP+_X") (class "Default")
      (node (ref "J3") (pin "2") (pinfunction "2-STEP+_2") (pintype "passive"))
      (node (ref "R9") (pin "2") (pinfunction "2_2") (pintype "passive"))
    )
    (net (code "101") (name "B_STEP+_Y") (class "Default")
      (node (ref "J5") (pin "2") (pinfunction "2-STEP+_2") (pintype "passive"))
      (node (ref "R17") (pin "2") (pinfunction "2_2") (pintype "passive"))
    )
    (net (code "102") (name "B_STEP+_Z") (class "Default")
      (node (ref "J9") (pin "2") (pinfunction "2-STEP+_2") (pintype "passive"))
      (node (ref "R33") (pin "2") (pinfunction "2_2") (pintype "passive"))
    )
    (net (code "103") (name "B_STEP-_A") (class "Default")
      (node (ref "J13") (pin "6") (pinfunction "6-STEP-_6") (pintype "passive"))
      (node (ref "LED49") (pin "2") (pinfunction "C_2") (pintype "passive"))
    )
    (net (code "104") (name "B_STEP-_C") (class "Default")
      (node (ref "J1") (pin "6") (pinfunction "6-STEP-_6") (pintype "passive"))
      (node (ref "LED1") (pin "2") (pinfunction "C_2") (pintype "passive"))
    )
    (net (code "105") (name "B_STEP-_WF") (class "Default")
      (node (ref "J17") (pin "6") (pinfunction "6-STEP-_6") (pintype "passive"))
      (node (ref "LED65") (pin "2") (pinfunction "C_2") (pintype "passive"))
    )
    (net (code "106") (name "B_STEP-_X") (class "Default")
      (node (ref "J3") (pin "6") (pinfunction "6-STEP-_6") (pintype "passive"))
      (node (ref "LED9") (pin "2") (pinfunction "C_2") (pintype "passive"))
    )
    (net (code "107") (name "B_STEP-_Y") (class "Default")
      (node (ref "J5") (pin "6") (pinfunction "6-STEP-_6") (pintype "passive"))
      (node (ref "LED17") (pin "2") (pinfunction "C_2") (pintype "passive"))
    )
    (net (code "108") (name "B_STEP-_Z") (class "Default")
      (node (ref "J9") (pin "6") (pinfunction "6-STEP-_6") (pintype "passive"))
      (node (ref "LED33") (pin "2") (pinfunction "C_2") (pintype "passive"))
    )
    (net (code "109") (name "N$25") (class "Default")
      (node (ref "J31") (pin "2") (pinfunction "2_2") (pintype "passive"))
      (node (ref "J32") (pin "P$2") (pinfunction "P$2_P$2") (pintype "bidirectional"))
      (node (ref "J32") (pin "P$3") (pinfunction "P$3_P$3") (pintype "bidirectional"))
    )
    (net (code "110") (name "Net-(LED1-A)") (class "Default")
      (node (ref "LED1") (pin "1") (pinfunction "A_1") (pintype "passive"))
      (node (ref "R1") (pin "1") (pinfunction "1_1") (pintype "passive"))
    )
    (net (code "111") (name "Net-(LED2-A)") (class "Default")
      (node (ref "LED2") (pin "1") (pinfunction "A_1") (pintype "passive"))
      (node (ref "R2") (pin "1") (pinfunction "1_1") (pintype "passive"))
    )
    (net (code "112") (name "Net-(LED3-A)") (class "Default")
      (node (ref "LED3") (pin "1") (pinfunction "A_1") (pintype "passive"))
      (node (ref "R3") (pin "1") (pinfunction "1_1") (pintype "passive"))
    )
    (net (code "113") (name "Net-(LED4-A)") (class "Default")
      (node (ref "LED4") (pin "1") (pinfunction "A_1") (pintype "passive"))
      (node (ref "R4") (pin "1") (pinfunction "1_1") (pintype "passive"))
    )
    (net (code "114") (name "Net-(LED5-A)") (class "Default")
      (node (ref "LED5") (pin "1") (pinfunction "A_1") (pintype "passive"))
      (node (ref "R5") (pin "1") (pinfunction "1_1") (pintype "passive"))
    )
    (net (code "115") (name "Net-(LED6-A)") (class "Default")
      (node (ref "LED6") (pin "1") (pinfunction "A_1") (pintype "passive"))
      (node (ref "R6") (pin "1") (pinfunction "1_1") (pintype "passive"))
    )
    (net (code "116") (name "Net-(LED7-A)") (class "Default")
      (node (ref "LED7") (pin "1") (pinfunction "A_1") (pintype "passive"))
      (node (ref "R7") (pin "1") (pinfunction "1_1") (pintype "passive"))
    )
    (net (code "117") (name "Net-(LED8-A)") (class "Default")
      (node (ref "LED8") (pin "1") (pinfunction "A_1") (pintype "passive"))
      (node (ref "R8") (pin "1") (pinfunction "1_1") (pintype "passive"))
    )
    (net (code "118") (name "Net-(LED9-A)") (class "Default")
      (node (ref "LED9") (pin "1") (pinfunction "A_1") (pintype "passive"))
      (node (ref "R9") (pin "1") (pinfunction "1_1") (pintype "passive"))
    )
    (net (code "119") (name "Net-(LED10-A)") (class "Default")
      (node (ref "LED10") (pin "1") (pinfunction "A_1") (pintype "passive"))
      (node (ref "R10") (pin "1") (pinfunction "1_1") (pintype "passive"))
    )
    (net (code "120") (name "Net-(LED11-A)") (class "Default")
      (node (ref "LED11") (pin "1") (pinfunction "A_1") (pintype "passive"))
      (node (ref "R11") (pin "1") (pinfunction "1_1") (pintype "passive"))
    )
    (net (code "121") (name "Net-(LED12-A)") (class "Default")
      (node (ref "LED12") (pin "1") (pinfunction "A_1") (pintype "passive"))
      (node (ref "R12") (pin "1") (pinfunction "1_1") (pintype "passive"))
    )
    (net (code "122") (name "Net-(LED13-A)") (class "Default")
      (node (ref "LED13") (pin "1") (pinfunction "A_1") (pintype "passive"))
      (node (ref "R13") (pin "1") (pinfunction "1_1") (pintype "passive"))
    )
    (net (code "123") (name "Net-(LED14-A)") (class "Default")
      (node (ref "LED14") (pin "1") (pinfunction "A_1") (pintype "passive"))
      (node (ref "R14") (pin "1") (pinfunction "1_1") (pintype "passive"))
    )
    (net (code "124") (name "Net-(LED15-A)") (class "Default")
      (node (ref "LED15") (pin "1") (pinfunction "A_1") (pintype "passive"))
      (node (ref "R15") (pin "1") (pinfunction "1_1") (pintype "passive"))
    )
    (net (code "125") (name "Net-(LED16-A)") (class "Default")
      (node (ref "LED16") (pin "1") (pinfunction "A_1") (pintype "passive"))
      (node (ref "R16") (pin "1") (pinfunction "1_1") (pintype "passive"))
    )
    (net (code "126") (name "Net-(LED17-A)") (class "Default")
      (node (ref "LED17") (pin "1") (pinfunction "A_1") (pintype "passive"))
      (node (ref "R17") (pin "1") (pinfunction "1_1") (pintype "passive"))
    )
    (net (code "127") (name "Net-(LED18-A)") (class "Default")
      (node (ref "LED18") (pin "1") (pinfunction "A_1") (pintype "passive"))
      (node (ref "R18") (pin "1") (pinfunction "1_1") (pintype "passive"))
    )
    (net (code "128") (name "Net-(LED19-A)") (class "Default")
      (node (ref "LED19") (pin "1") (pinfunction "A_1") (pintype "passive"))
      (node (ref "R19") (pin "1") (pinfunction "1_1") (pintype "passive"))
    )
    (net (code "129") (name "Net-(LED20-A)") (class "Default")
      (node (ref "LED20") (pin "1") (pinfunction "A_1") (pintype "passive"))
      (node (ref "R20") (pin "1") (pinfunction "1_1") (pintype "passive"))
    )
    (net (code "130") (name "Net-(LED21-A)") (class "Default")
      (node (ref "LED21") (pin "1") (pinfunction "A_1") (pintype "passive"))
      (node (ref "R21") (pin "1") (pinfunction "1_1") (pintype "passive"))
    )
    (net (code "131") (name "Net-(LED22-A)") (class "Default")
      (node (ref "LED22") (pin "1") (pinfunction "A_1") (pintype "passive"))
      (node (ref "R22") (pin "1") (pinfunction "1_1") (pintype "passive"))
    )
    (net (code "132") (name "Net-(LED23-A)") (class "Default")
      (node (ref "LED23") (pin "1") (pinfunction "A_1") (pintype "passive"))
      (node (ref "R23") (pin "1") (pinfunction "1_1") (pintype "passive"))
    )
    (net (code "133") (name "Net-(LED24-A)") (class "Default")
      (node (ref "LED24") (pin "1") (pinfunction "A_1") (pintype "passive"))
      (node (ref "R24") (pin "1") (pinfunction "1_1") (pintype "passive"))
    )
    (net (code "134") (name "Net-(LED25-A)") (class "Default")
      (node (ref "LED25") (pin "1") (pinfunction "A_1") (pintype "passive"))
      (node (ref "R27") (pin "P$2") (pinfunction "2_P$2") (pintype "passive"))
      (node (ref "U1") (pin "1") (pinfunction "B(2)_1") (pintype "input"))
    )
    (net (code "135") (name "Net-(LED25-C)") (class "Default")
      (node (ref "LED25") (pin "2") (pinfunction "C_2") (pintype "passive"))
      (node (ref "R29") (pin "P$2") (pinfunction "2_P$2") (pintype "passive"))
      (node (ref "SW2") (pin "1") (pinfunction "1_1") (pintype "passive"))
      (node (ref "SW2") (pin "2") (pinfunction "2_2") (pintype "passive"))
    )
    (net (code "136") (name "Net-(LED28-A)") (class "Default")
      (node (ref "LED28") (pin "1") (pinfunction "A_1") (pintype "passive"))
      (node (ref "R41") (pin "P$2") (pinfunction "2_P$2") (pintype "passive"))
      (node (ref "U3") (pin "1") (pinfunction "B(2)_1") (pintype "input"))
    )
    (net (code "137") (name "Net-(LED28-C)") (class "Default")
      (node (ref "LED28") (pin "2") (pinfunction "C_2") (pintype "passive"))
      (node (ref "R43") (pin "P$2") (pinfunction "2_P$2") (pintype "passive"))
      (node (ref "SW4") (pin "1") (pinfunction "1_1") (pintype "passive"))
      (node (ref "SW4") (pin "2") (pinfunction "2_2") (pintype "passive"))
    )
    (net (code "138") (name "Net-(LED30-A)") (class "Default")
      (node (ref "LED30") (pin "1") (pinfunction "A_1") (pintype "passive"))
      (node (ref "R47") (pin "P$2") (pinfunction "2_P$2") (pintype "passive"))
      (node (ref "U5") (pin "1") (pinfunction "B(2)_1") (pintype "input"))
    )
    (net (code "139") (name "Net-(LED30-C)") (class "Default")
      (node (ref "LED30") (pin "2") (pinfunction "C_2") (pintype "passive"))
      (node (ref "R57") (pin "P$2") (pinfunction "2_P$2") (pintype "passive"))
      (node (ref "SW6") (pin "1") (pinfunction "1_1") (pintype "passive"))
      (node (ref "SW6") (pin "2") (pinfunction "2_2") (pintype "passive"))
    )
    (net (code "140") (name "Net-(LED32-A)") (class "Default")
      (node (ref "LED32") (pin "1") (pinfunction "A_1") (pintype "passive"))
      (node (ref "R62") (pin "P$2") (pinfunction "2_P$2") (pintype "passive"))
      (node (ref "U7") (pin "1") (pinfunction "B(2)_1") (pintype "input"))
    )
    (net (code "141") (name "Net-(LED32-C)") (class "Default")
      (node (ref "LED32") (pin "2") (pinfunction "C_2") (pintype "passive"))
      (node (ref "R64") (pin "P$2") (pinfunction "2_P$2") (pintype "passive"))
      (node (ref "SW8") (pin "1") (pinfunction "1_1") (pintype "passive"))
      (node (ref "SW8") (pin "2") (pinfunction "2_2") (pintype "passive"))
    )
    (net (code "142") (name "Net-(LED33-A)") (class "Default")
      (node (ref "LED33") (pin "1") (pinfunction "A_1") (pintype "passive"))
      (node (ref "R33") (pin "1") (pinfunction "1_1") (pintype "passive"))
    )
    (net (code "143") (name "Net-(LED34-A)") (class "Default")
      (node (ref "LED34") (pin "1") (pinfunction "A_1") (pintype "passive"))
      (node (ref "R34") (pin "1") (pinfunction "1_1") (pintype "passive"))
    )
    (net (code "144") (name "Net-(LED35-A)") (class "Default")
      (node (ref "LED35") (pin "1") (pinfunction "A_1") (pintype "passive"))
      (node (ref "R35") (pin "1") (pinfunction "1_1") (pintype "passive"))
    )
    (net (code "145") (name "Net-(LED36-A)") (class "Default")
      (node (ref "LED36") (pin "1") (pinfunction "A_1") (pintype "passive"))
      (node (ref "R36") (pin "1") (pinfunction "1_1") (pintype "passive"))
    )
    (net (code "146") (name "Net-(LED37-A)") (class "Default")
      (node (ref "LED37") (pin "1") (pinfunction "A_1") (pintype "passive"))
      (node (ref "R37") (pin "1") (pinfunction "1_1") (pintype "passive"))
    )
    (net (code "147") (name "Net-(LED38-A)") (class "Default")
      (node (ref "LED38") (pin "1") (pinfunction "A_1") (pintype "passive"))
      (node (ref "R38") (pin "1") (pinfunction "1_1") (pintype "passive"))
    )
    (net (code "148") (name "Net-(LED39-A)") (class "Default")
      (node (ref "LED39") (pin "1") (pinfunction "A_1") (pintype "passive"))
      (node (ref "R39") (pin "1") (pinfunction "1_1") (pintype "passive"))
    )
    (net (code "149") (name "Net-(LED40-A)") (class "Default")
      (node (ref "LED40") (pin "1") (pinfunction "A_1") (pintype "passive"))
      (node (ref "R40") (pin "1") (pinfunction "1_1") (pintype "passive"))
    )
    (net (code "150") (name "Net-(LED42-A)") (class "Default")
      (node (ref "LED42") (pin "1") (pinfunction "A_1") (pintype "passive"))
      (node (ref "R76") (pin "P$2") (pinfunction "2_P$2") (pintype "passive"))
      (node (ref "U9") (pin "1") (pinfunction "B(2)_1") (pintype "input"))
    )
    (net (code "151") (name "Net-(LED42-C)") (class "Default")
      (node (ref "LED42") (pin "2") (pinfunction "C_2") (pintype "passive"))
      (node (ref "R78") (pin "P$2") (pinfunction "2_P$2") (pintype "passive"))
      (node (ref "SW10") (pin "1") (pinfunction "1_1") (pintype "passive"))
      (node (ref "SW10") (pin "2") (pinfunction "2_2") (pintype "passive"))
    )
    (net (code "152") (name "Net-(LED44-A)") (class "Default")
      (node (ref "LED44") (pin "1") (pinfunction "A_1") (pintype "passive"))
      (node (ref "R82") (pin "P$2") (pinfunction "2_P$2") (pintype "passive"))
      (node (ref "U11") (pin "1") (pinfunction "B(2)_1") (pintype "input"))
    )
    (net (code "153") (name "Net-(LED44-C)") (class "Default")
      (node (ref "LED44") (pin "2") (pinfunction "C_2") (pintype "passive"))
      (node (ref "R84") (pin "P$2") (pinfunction "2_P$2") (pintype "passive"))
      (node (ref "SW12") (pin "1") (pinfunction "1_1") (pintype "passive"))
      (node (ref "SW12") (pin "2") (pinfunction "2_2") (pintype "passive"))
    )
    (net (code "154") (name "Net-(LED46-A)") (class "Default")
      (node (ref "LED46") (pin "1") (pinfunction "A_1") (pintype "passive"))
      (node (ref "R88") (pin "P$2") (pinfunction "2_P$2") (pintype "passive"))
      (node (ref "U13") (pin "1") (pinfunction "B(2)_1") (pintype "input"))
    )
    (net (code "155") (name "Net-(LED46-C)") (class "Default")
      (node (ref "LED46") (pin "2") (pinfunction "C_2") (pintype "passive"))
      (node (ref "R90") (pin "P$2") (pinfunction "2_P$2") (pintype "passive"))
      (node (ref "SW14") (pin "1") (pinfunction "1_1") (pintype "passive"))
      (node (ref "SW14") (pin "2") (pinfunction "2_2") (pintype "passive"))
    )
    (net (code "156") (name "Net-(LED48-A)") (class "Default")
      (node (ref "LED48") (pin "1") (pinfunction "A_1") (pintype "passive"))
      (node (ref "R94") (pin "P$2") (pinfunction "2_P$2") (pintype "passive"))
      (node (ref "U15") (pin "1") (pinfunction "B(2)_1") (pintype "input"))
    )
    (net (code "157") (name "Net-(LED48-C)") (class "Default")
      (node (ref "LED48") (pin "2") (pinfunction "C_2") (pintype "passive"))
      (node (ref "R96") (pin "P$2") (pinfunction "2_P$2") (pintype "passive"))
      (node (ref "SW16") (pin "1") (pinfunction "1_1") (pintype "passive"))
      (node (ref "SW16") (pin "2") (pinfunction "2_2") (pintype "passive"))
    )
    (net (code "158") (name "Net-(LED49-A)") (class "Default")
      (node (ref "LED49") (pin "1") (pinfunction "A_1") (pintype "passive"))
      (node (ref "R49") (pin "1") (pinfunction "1_1") (pintype "passive"))
    )
    (net (code "159") (name "Net-(LED50-A)") (class "Default")
      (node (ref "LED50") (pin "1") (pinfunction "A_1") (pintype "passive"))
      (node (ref "R50") (pin "1") (pinfunction "1_1") (pintype "passive"))
    )
    (net (code "160") (name "Net-(LED51-A)") (class "Default")
      (node (ref "LED51") (pin "1") (pinfunction "A_1") (pintype "passive"))
      (node (ref "R51") (pin "1") (pinfunction "1_1") (pintype "passive"))
    )
    (net (code "161") (name "Net-(LED52-A)") (class "Default")
      (node (ref "LED52") (pin "1") (pinfunction "A_1") (pintype "passive"))
      (node (ref "R52") (pin "1") (pinfunction "1_1") (pintype "passive"))
    )
    (net (code "162") (name "Net-(LED53-A)") (class "Default")
      (node (ref "LED53") (pin "1") (pinfunction "A_1") (pintype "passive"))
      (node (ref "R53") (pin "1") (pinfunction "1_1") (pintype "passive"))
    )
    (net (code "163") (name "Net-(LED54-A)") (class "Default")
      (node (ref "LED54") (pin "1") (pinfunction "A_1") (pintype "passive"))
      (node (ref "R54") (pin "1") (pinfunction "1_1") (pintype "passive"))
    )
    (net (code "164") (name "Net-(LED55-A)") (class "Default")
      (node (ref "LED55") (pin "1") (pinfunction "A_1") (pintype "passive"))
      (node (ref "R55") (pin "1") (pinfunction "1_1") (pintype "passive"))
    )
    (net (code "165") (name "Net-(LED56-A)") (class "Default")
      (node (ref "LED56") (pin "1") (pinfunction "A_1") (pintype "passive"))
      (node (ref "R56") (pin "1") (pinfunction "1_1") (pintype "passive"))
    )
    (net (code "166") (name "Net-(LED58-A)") (class "Default")
      (node (ref "LED58") (pin "1") (pinfunction "A_1") (pintype "passive"))
      (node (ref "R100") (pin "P$2") (pinfunction "2_P$2") (pintype "passive"))
      (node (ref "U17") (pin "1") (pinfunction "B(2)_1") (pintype "input"))
    )
    (net (code "167") (name "Net-(LED58-C)") (class "Default")
      (node (ref "LED58") (pin "2") (pinfunction "C_2") (pintype "passive"))
      (node (ref "R102") (pin "P$2") (pinfunction "2_P$2") (pintype "passive"))
      (node (ref "SW18") (pin "1") (pinfunction "1_1") (pintype "passive"))
      (node (ref "SW18") (pin "2") (pinfunction "2_2") (pintype "passive"))
    )
    (net (code "168") (name "Net-(LED60-A)") (class "Default")
      (node (ref "LED60") (pin "1") (pinfunction "A_1") (pintype "passive"))
      (node (ref "R106") (pin "P$2") (pinfunction "2_P$2") (pintype "passive"))
      (node (ref "U20") (pin "1") (pinfunction "B(2)_1") (pintype "input"))
    )
    (net (code "169") (name "Net-(LED60-C)") (class "Default")
      (node (ref "LED60") (pin "2") (pinfunction "C_2") (pintype "passive"))
      (node (ref "R108") (pin "P$2") (pinfunction "2_P$2") (pintype "passive"))
      (node (ref "SW20") (pin "1") (pinfunction "1_1") (pintype "passive"))
      (node (ref "SW20") (pin "2") (pinfunction "2_2") (pintype "passive"))
    )
    (net (code "170") (name "Net-(LED65-A)") (class "Default")
      (node (ref "LED65") (pin "1") (pinfunction "A_1") (pintype "passive"))
      (node (ref "R65") (pin "1") (pinfunction "1_1") (pintype "passive"))
    )
    (net (code "171") (name "Net-(LED66-A)") (class "Default")
      (node (ref "LED66") (pin "1") (pinfunction "A_1") (pintype "passive"))
      (node (ref "R66") (pin "1") (pinfunction "1_1") (pintype "passive"))
    )
    (net (code "172") (name "Net-(LED67-A)") (class "Default")
      (node (ref "LED67") (pin "1") (pinfunction "A_1") (pintype "passive"))
      (node (ref "R67") (pin "1") (pinfunction "1_1") (pintype "passive"))
    )
    (net (code "173") (name "Net-(LED68-A)") (class "Default")
      (node (ref "LED68") (pin "1") (pinfunction "A_1") (pintype "passive"))
      (node (ref "R68") (pin "1") (pinfunction "1_1") (pintype "passive"))
    )
    (net (code "174") (name "Net-(LED69-A)") (class "Default")
      (node (ref "LED69") (pin "1") (pinfunction "A_1") (pintype "passive"))
      (node (ref "R69") (pin "1") (pinfunction "1_1") (pintype "passive"))
    )
    (net (code "175") (name "Net-(LED70-A)") (class "Default")
      (node (ref "LED70") (pin "1") (pinfunction "A_1") (pintype "passive"))
      (node (ref "R70") (pin "1") (pinfunction "1_1") (pintype "passive"))
    )
    (net (code "176") (name "Net-(LED71-A)") (class "Default")
      (node (ref "LED71") (pin "1") (pinfunction "A_1") (pintype "passive"))
      (node (ref "R71") (pin "1") (pinfunction "1_1") (pintype "passive"))
    )
    (net (code "177") (name "Net-(LED72-A)") (class "Default")
      (node (ref "LED72") (pin "1") (pinfunction "A_1") (pintype "passive"))
      (node (ref "R72") (pin "1") (pinfunction "1_1") (pintype "passive"))
    )
    (net (code "178") (name "Net-(R28-2)") (class "Default")
      (node (ref "R28") (pin "P$2") (pinfunction "2_P$2") (pintype "passive"))
      (node (ref "U1") (pin "2") (pinfunction "E(1)_2") (pintype "output"))
    )
    (net (code "179") (name "Net-(R42-2)") (class "Default")
      (node (ref "R42") (pin "P$2") (pinfunction "2_P$2") (pintype "passive"))
      (node (ref "U3") (pin "2") (pinfunction "E(1)_2") (pintype "output"))
    )
    (net (code "180") (name "Net-(R48-2)") (class "Default")
      (node (ref "R48") (pin "P$2") (pinfunction "2_P$2") (pintype "passive"))
      (node (ref "U5") (pin "2") (pinfunction "E(1)_2") (pintype "output"))
    )
    (net (code "181") (name "Net-(R63-2)") (class "Default")
      (node (ref "R63") (pin "P$2") (pinfunction "2_P$2") (pintype "passive"))
      (node (ref "U7") (pin "2") (pinfunction "E(1)_2") (pintype "output"))
    )
    (net (code "182") (name "Net-(R77-2)") (class "Default")
      (node (ref "R77") (pin "P$2") (pinfunction "2_P$2") (pintype "passive"))
      (node (ref "U9") (pin "2") (pinfunction "E(1)_2") (pintype "output"))
    )
    (net (code "183") (name "Net-(R83-2)") (class "Default")
      (node (ref "R83") (pin "P$2") (pinfunction "2_P$2") (pintype "passive"))
      (node (ref "U11") (pin "2") (pinfunction "E(1)_2") (pintype "output"))
    )
    (net (code "184") (name "Net-(R89-2)") (class "Default")
      (node (ref "R89") (pin "P$2") (pinfunction "2_P$2") (pintype "passive"))
      (node (ref "U13") (pin "2") (pinfunction "E(1)_2") (pintype "output"))
    )
    (net (code "185") (name "Net-(R95-2)") (class "Default")
      (node (ref "R95") (pin "P$2") (pinfunction "2_P$2") (pintype "passive"))
      (node (ref "U15") (pin "2") (pinfunction "E(1)_2") (pintype "output"))
    )
    (net (code "186") (name "Net-(R101-2)") (class "Default")
      (node (ref "R101") (pin "P$2") (pinfunction "2_P$2") (pintype "passive"))
      (node (ref "U17") (pin "2") (pinfunction "E(1)_2") (pintype "output"))
    )
    (net (code "187") (name "Net-(R107-2)") (class "Default")
      (node (ref "R107") (pin "P$2") (pinfunction "2_P$2") (pintype "passive"))
      (node (ref "U20") (pin "2") (pinfunction "E(1)_2") (pintype "output"))
    )
  )
)
